# module_decoding_a.net
KiCad netlist of a schematic drawn in EAGLE
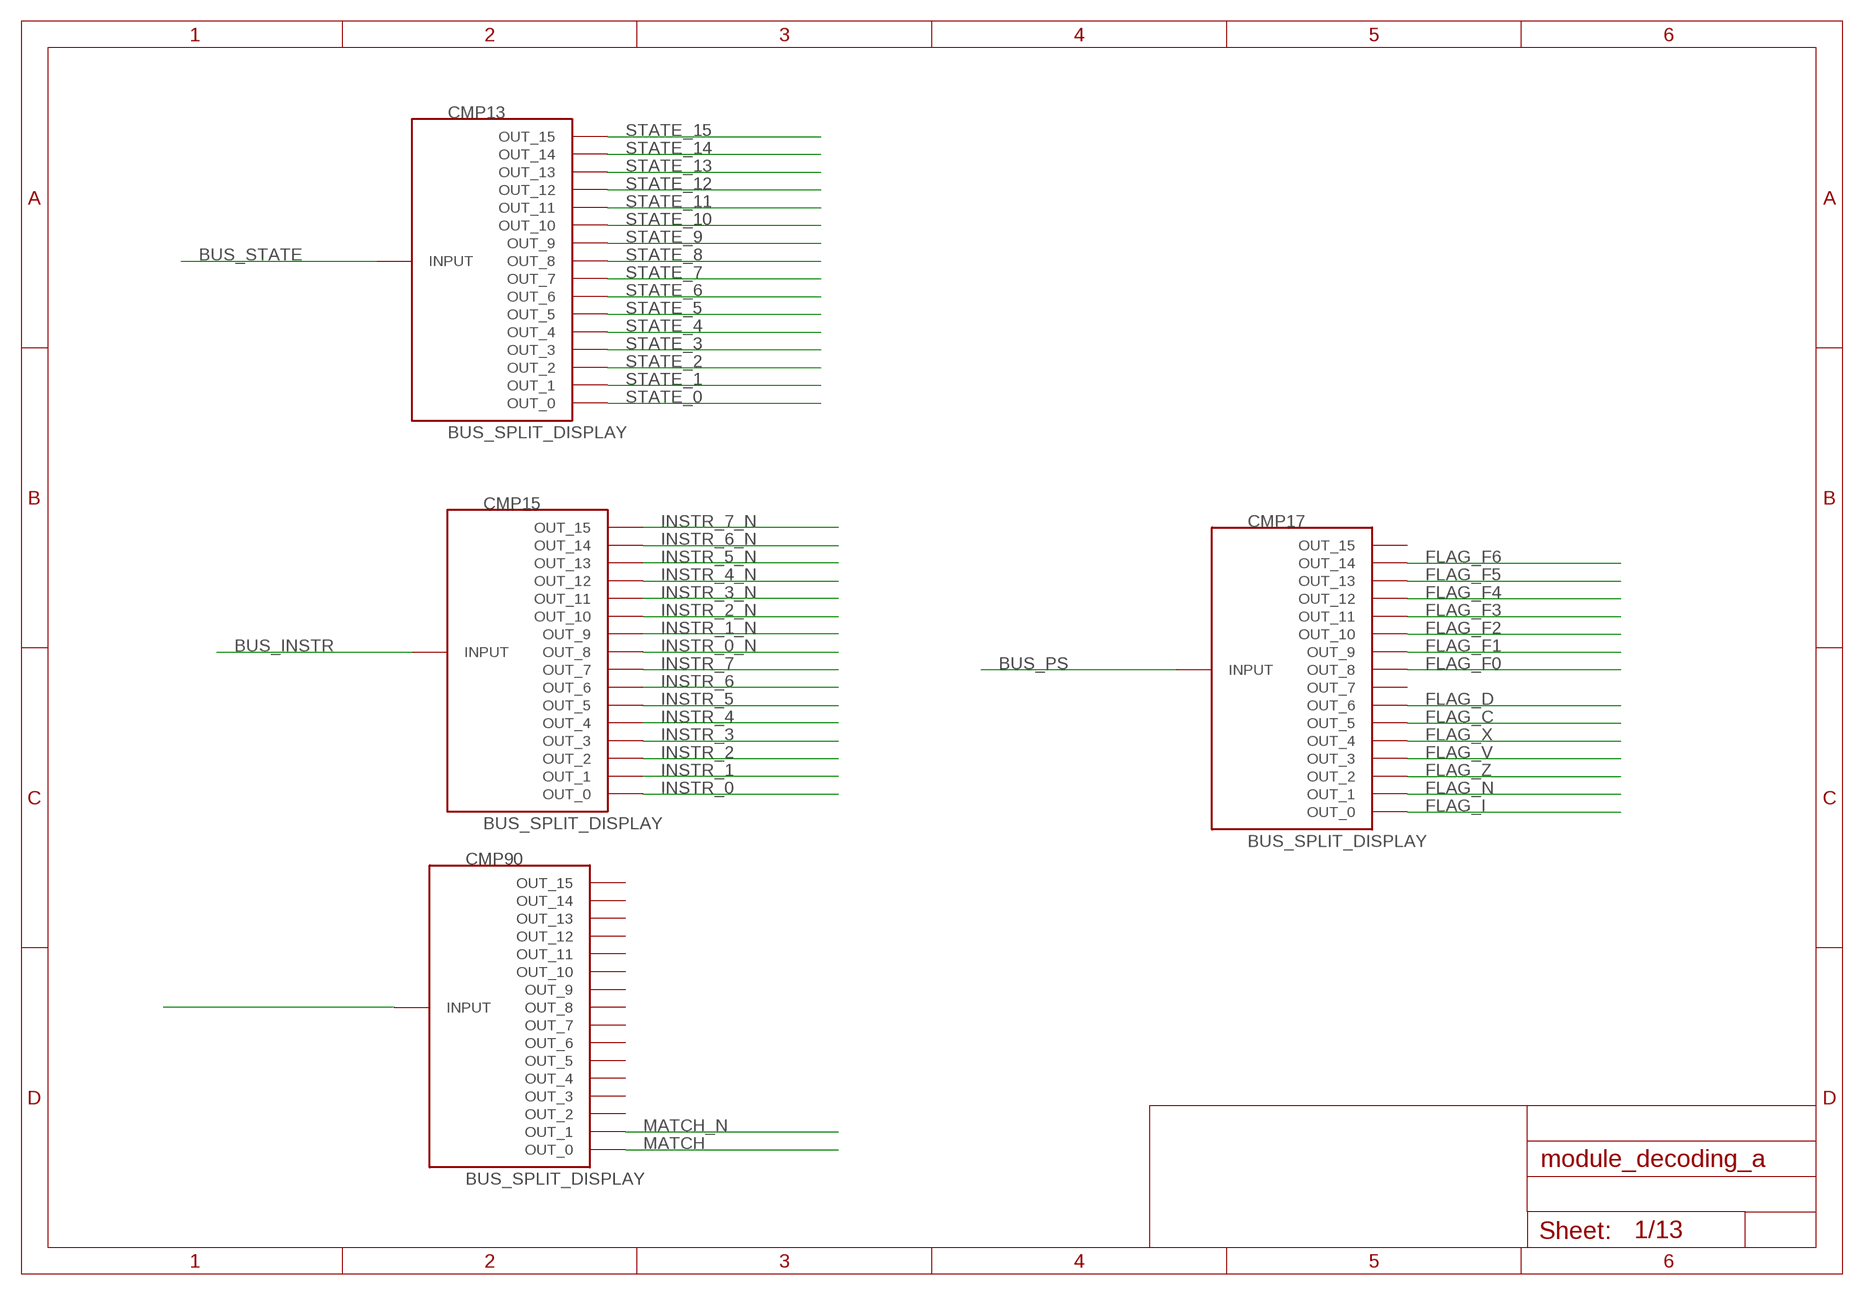
[diagram p0: schematic, sheet 1]
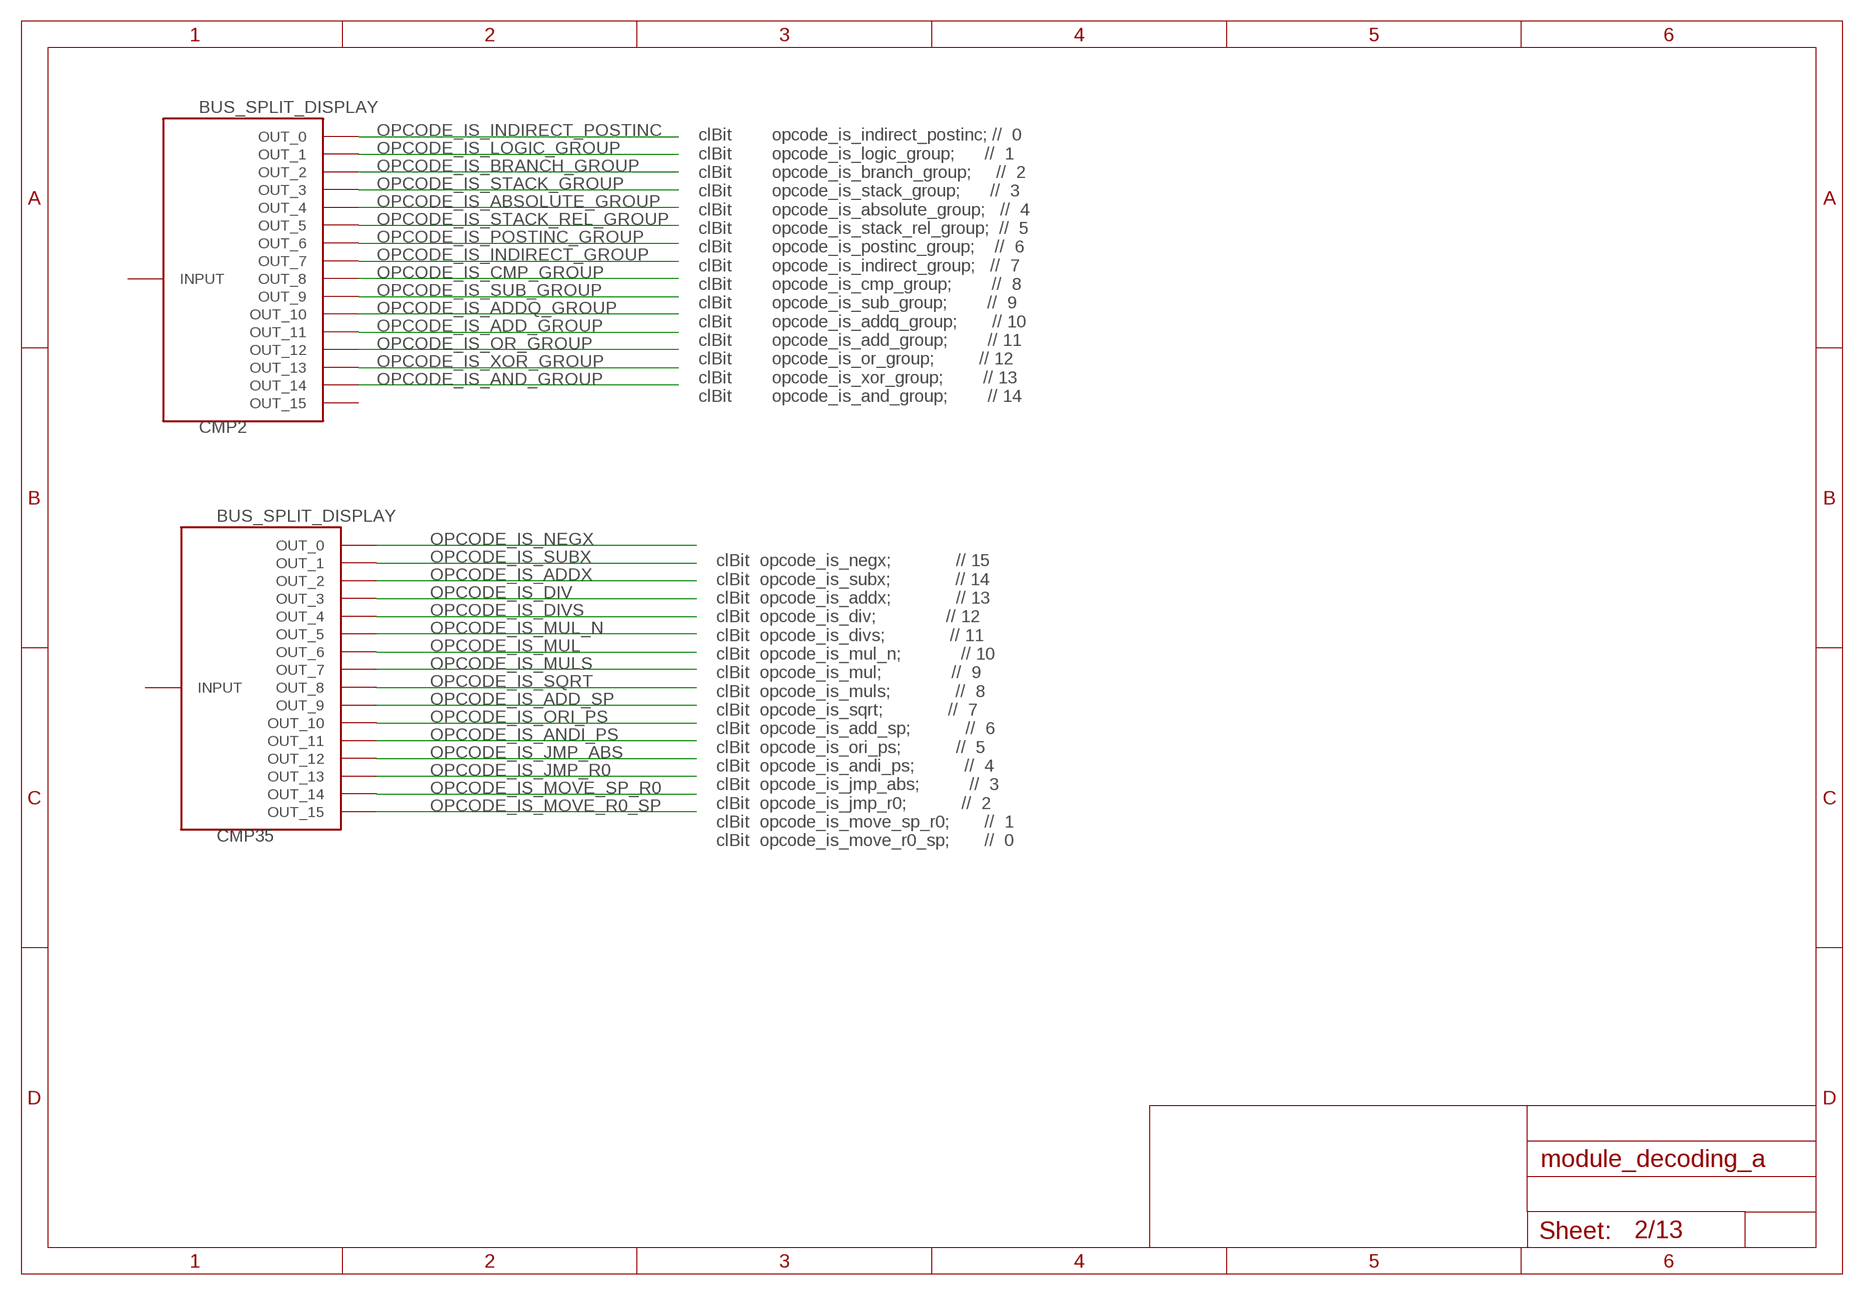
[diagram p1: schematic, sheet 2]
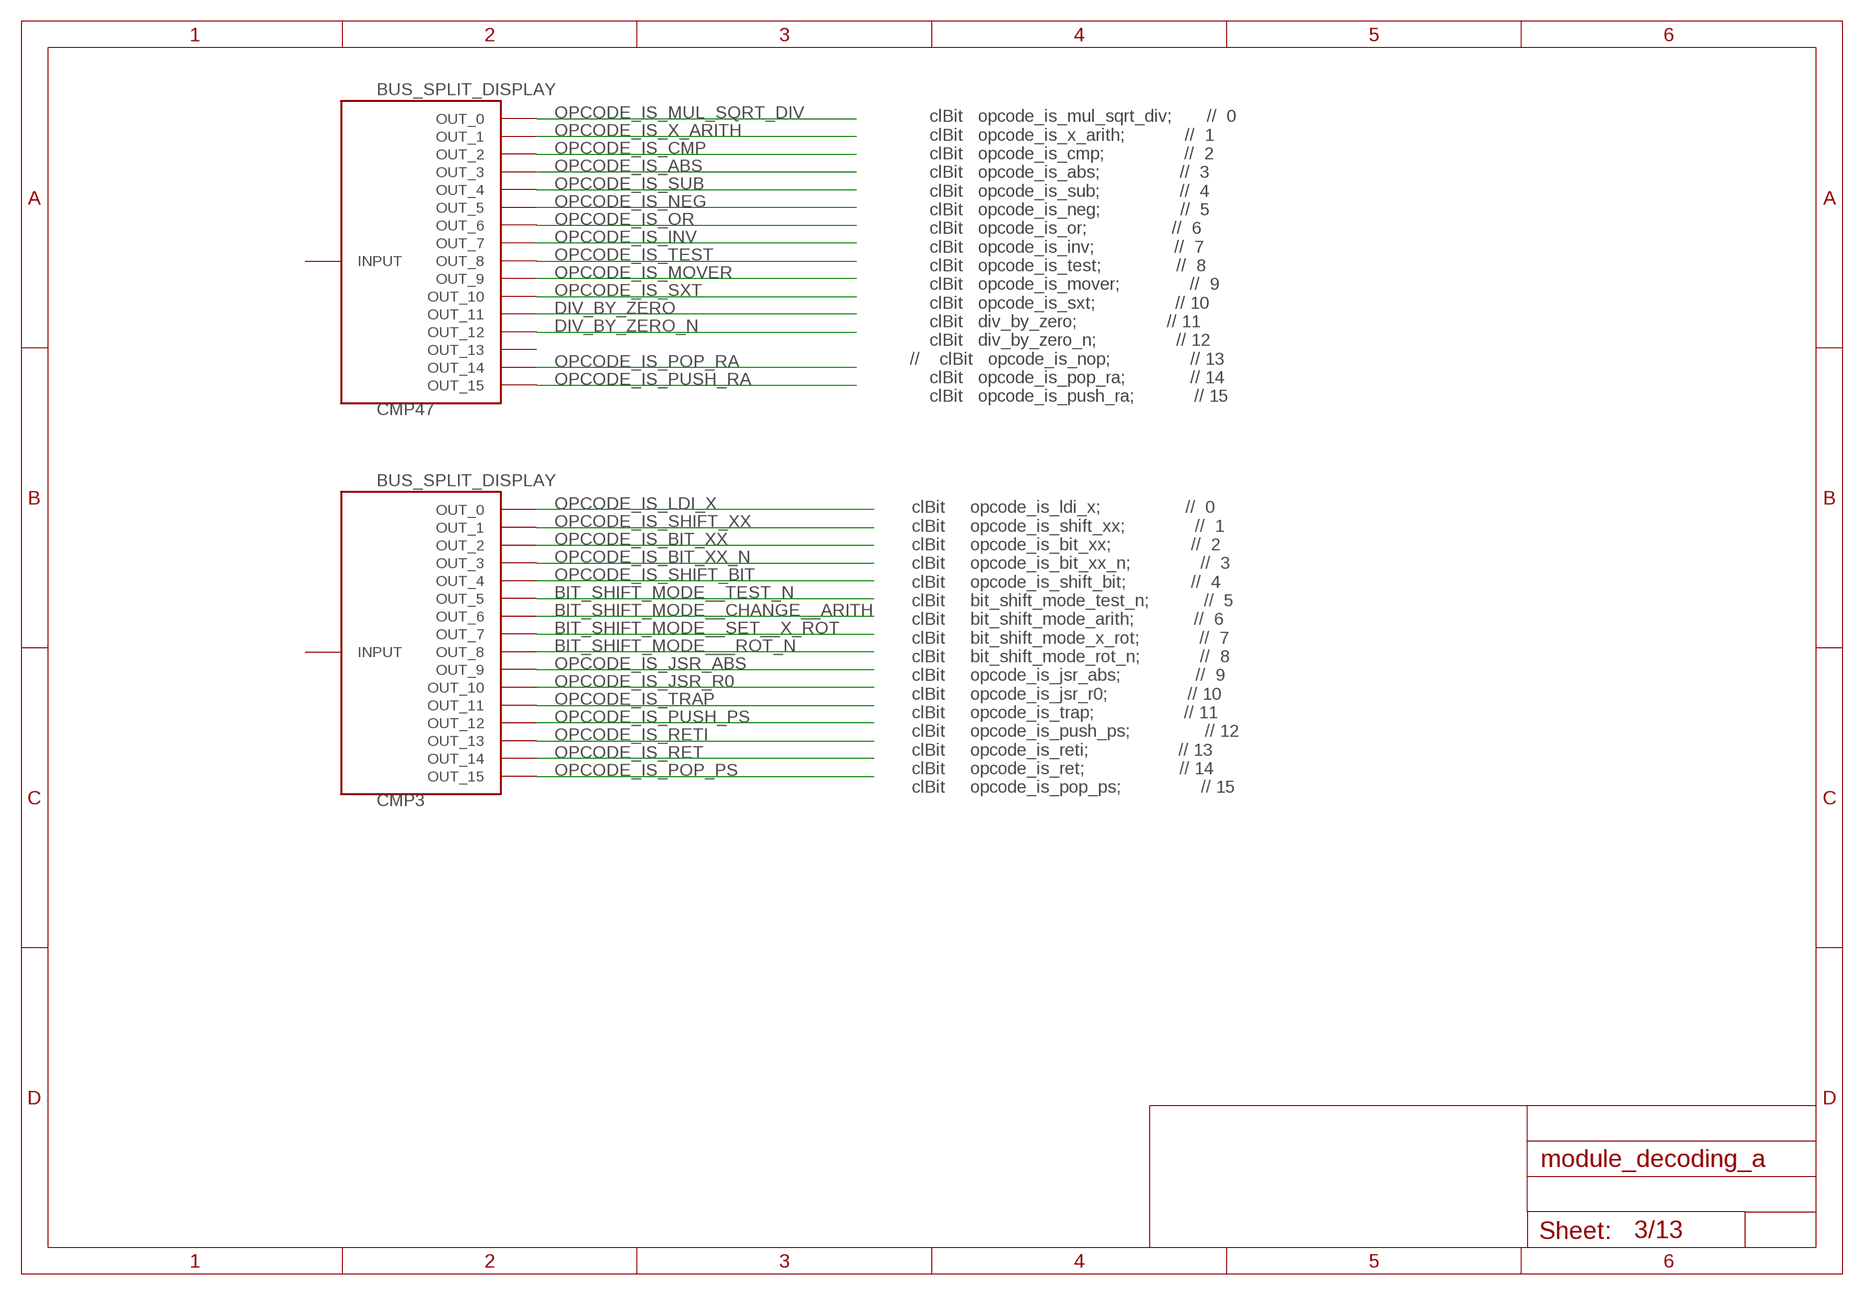
[diagram p2: schematic, sheet 3]
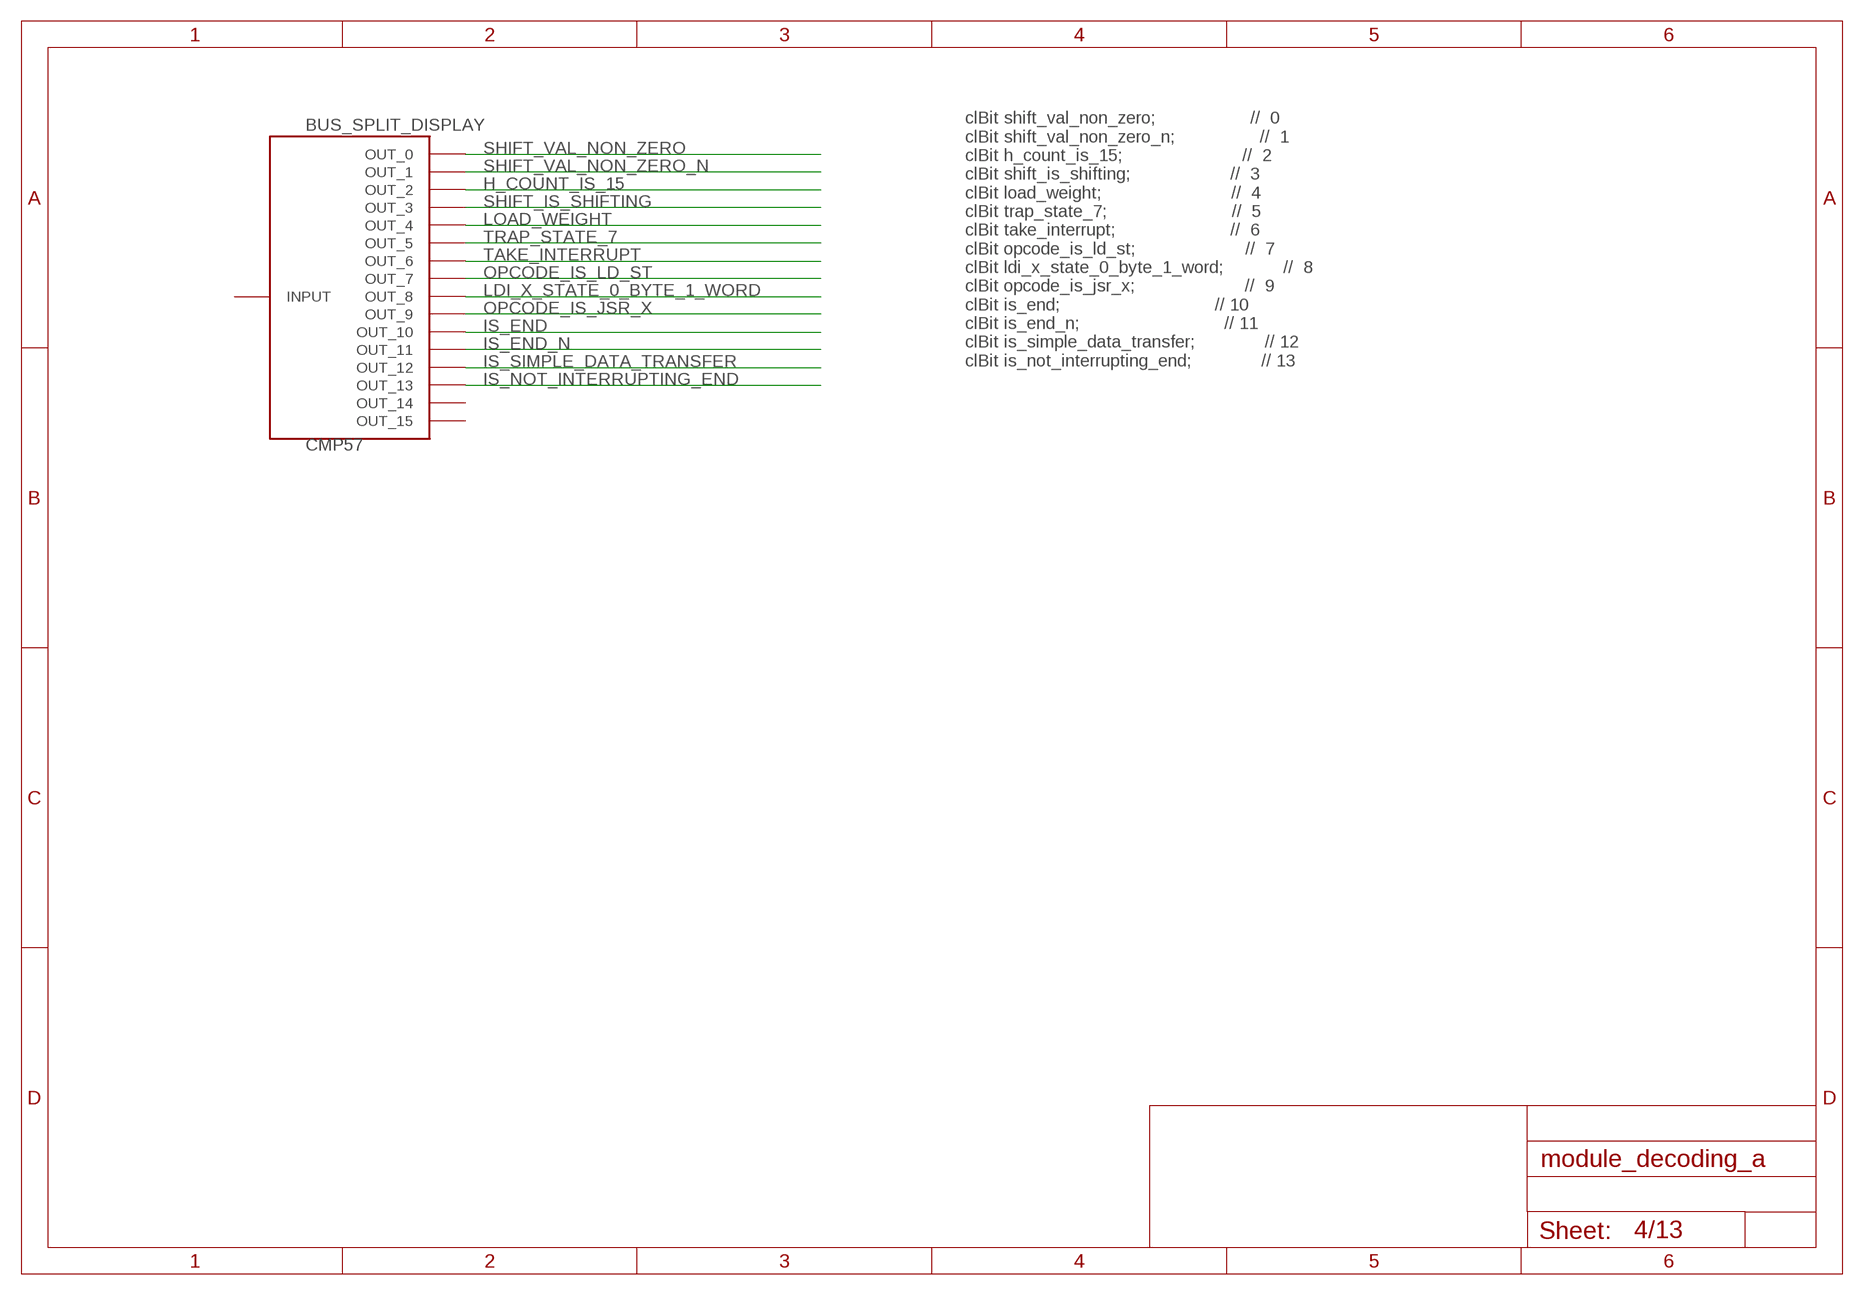
[diagram p3: schematic, sheet 4]
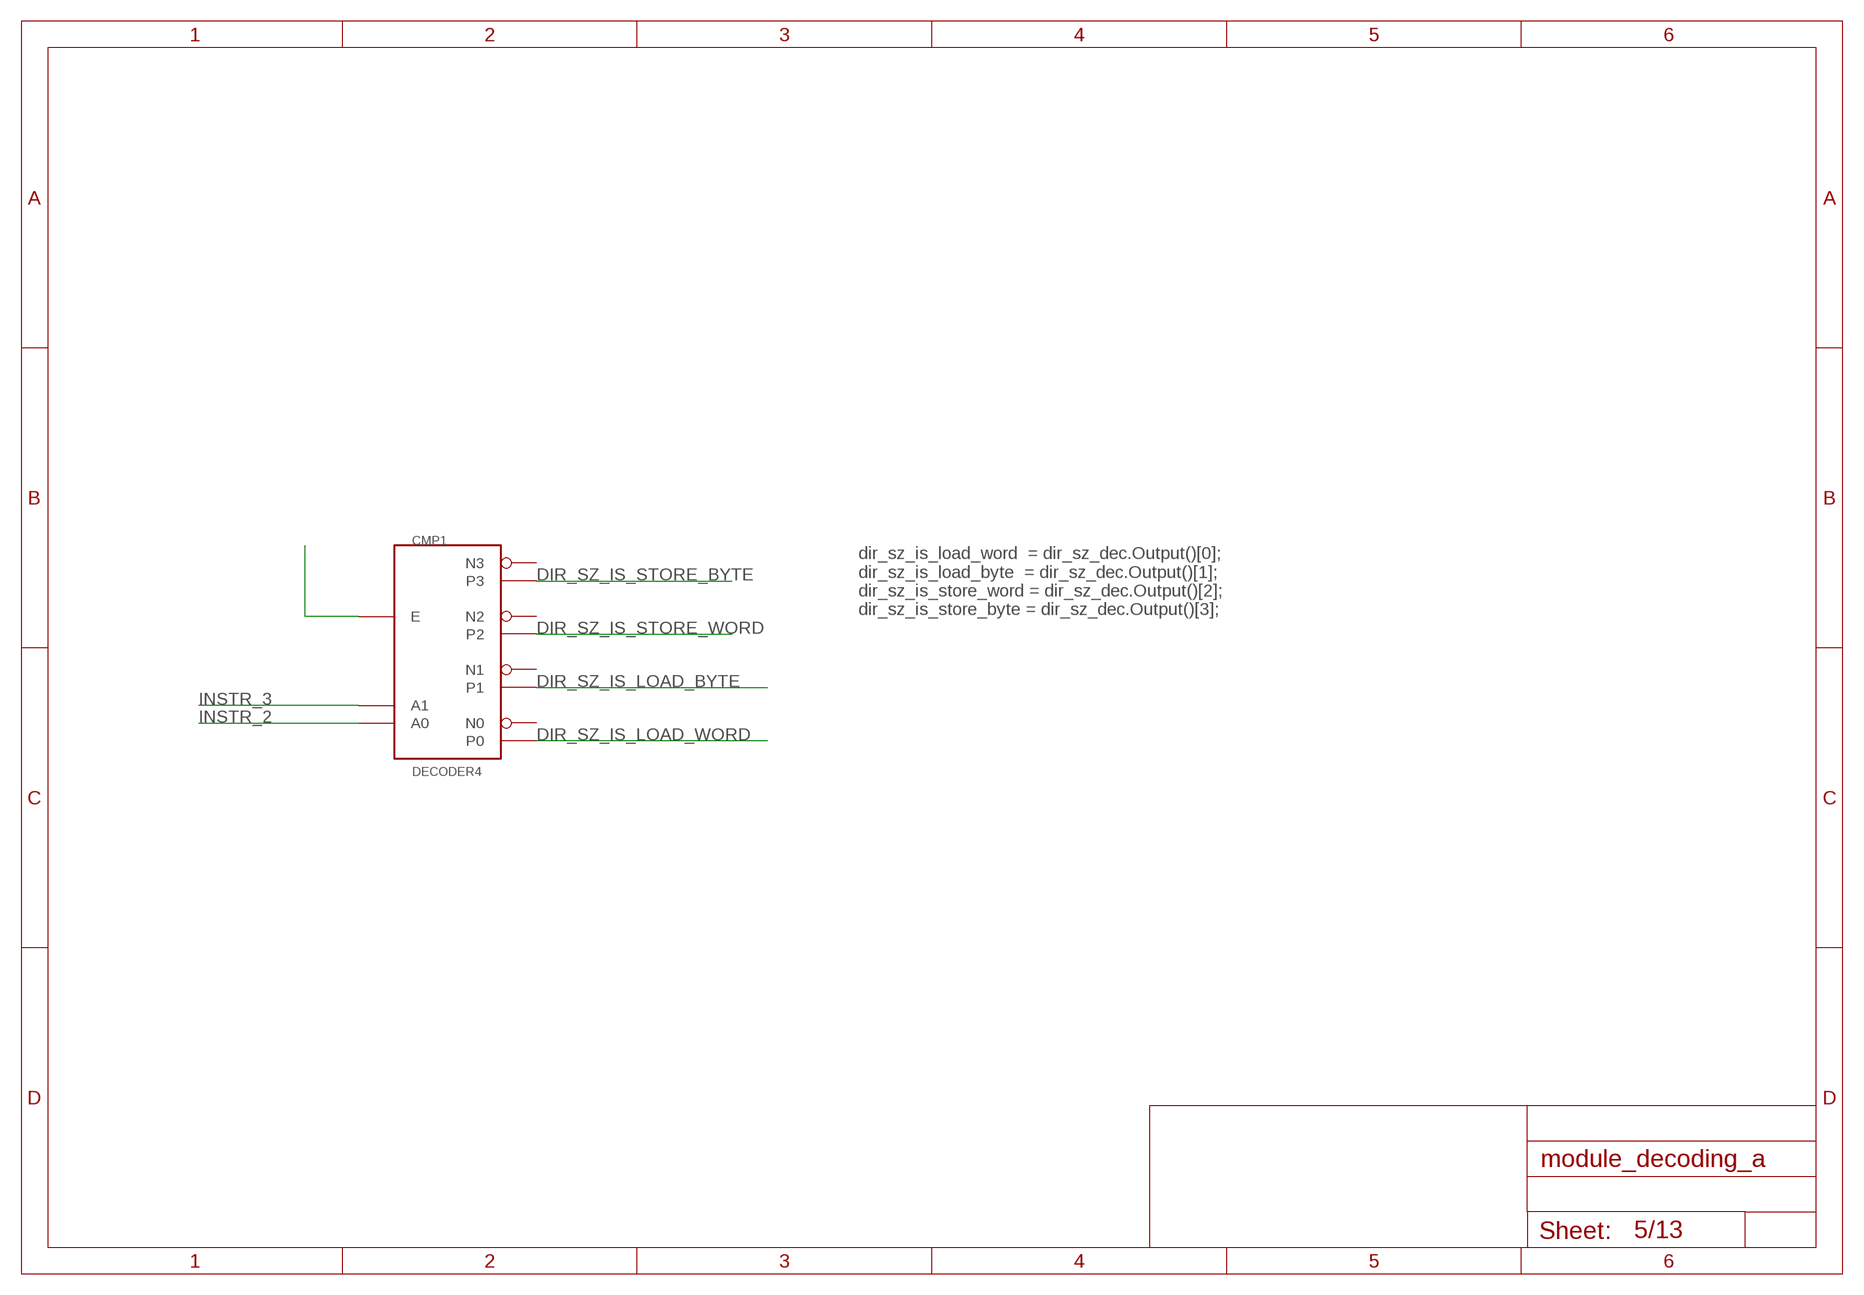
[diagram p4: schematic, sheet 5]
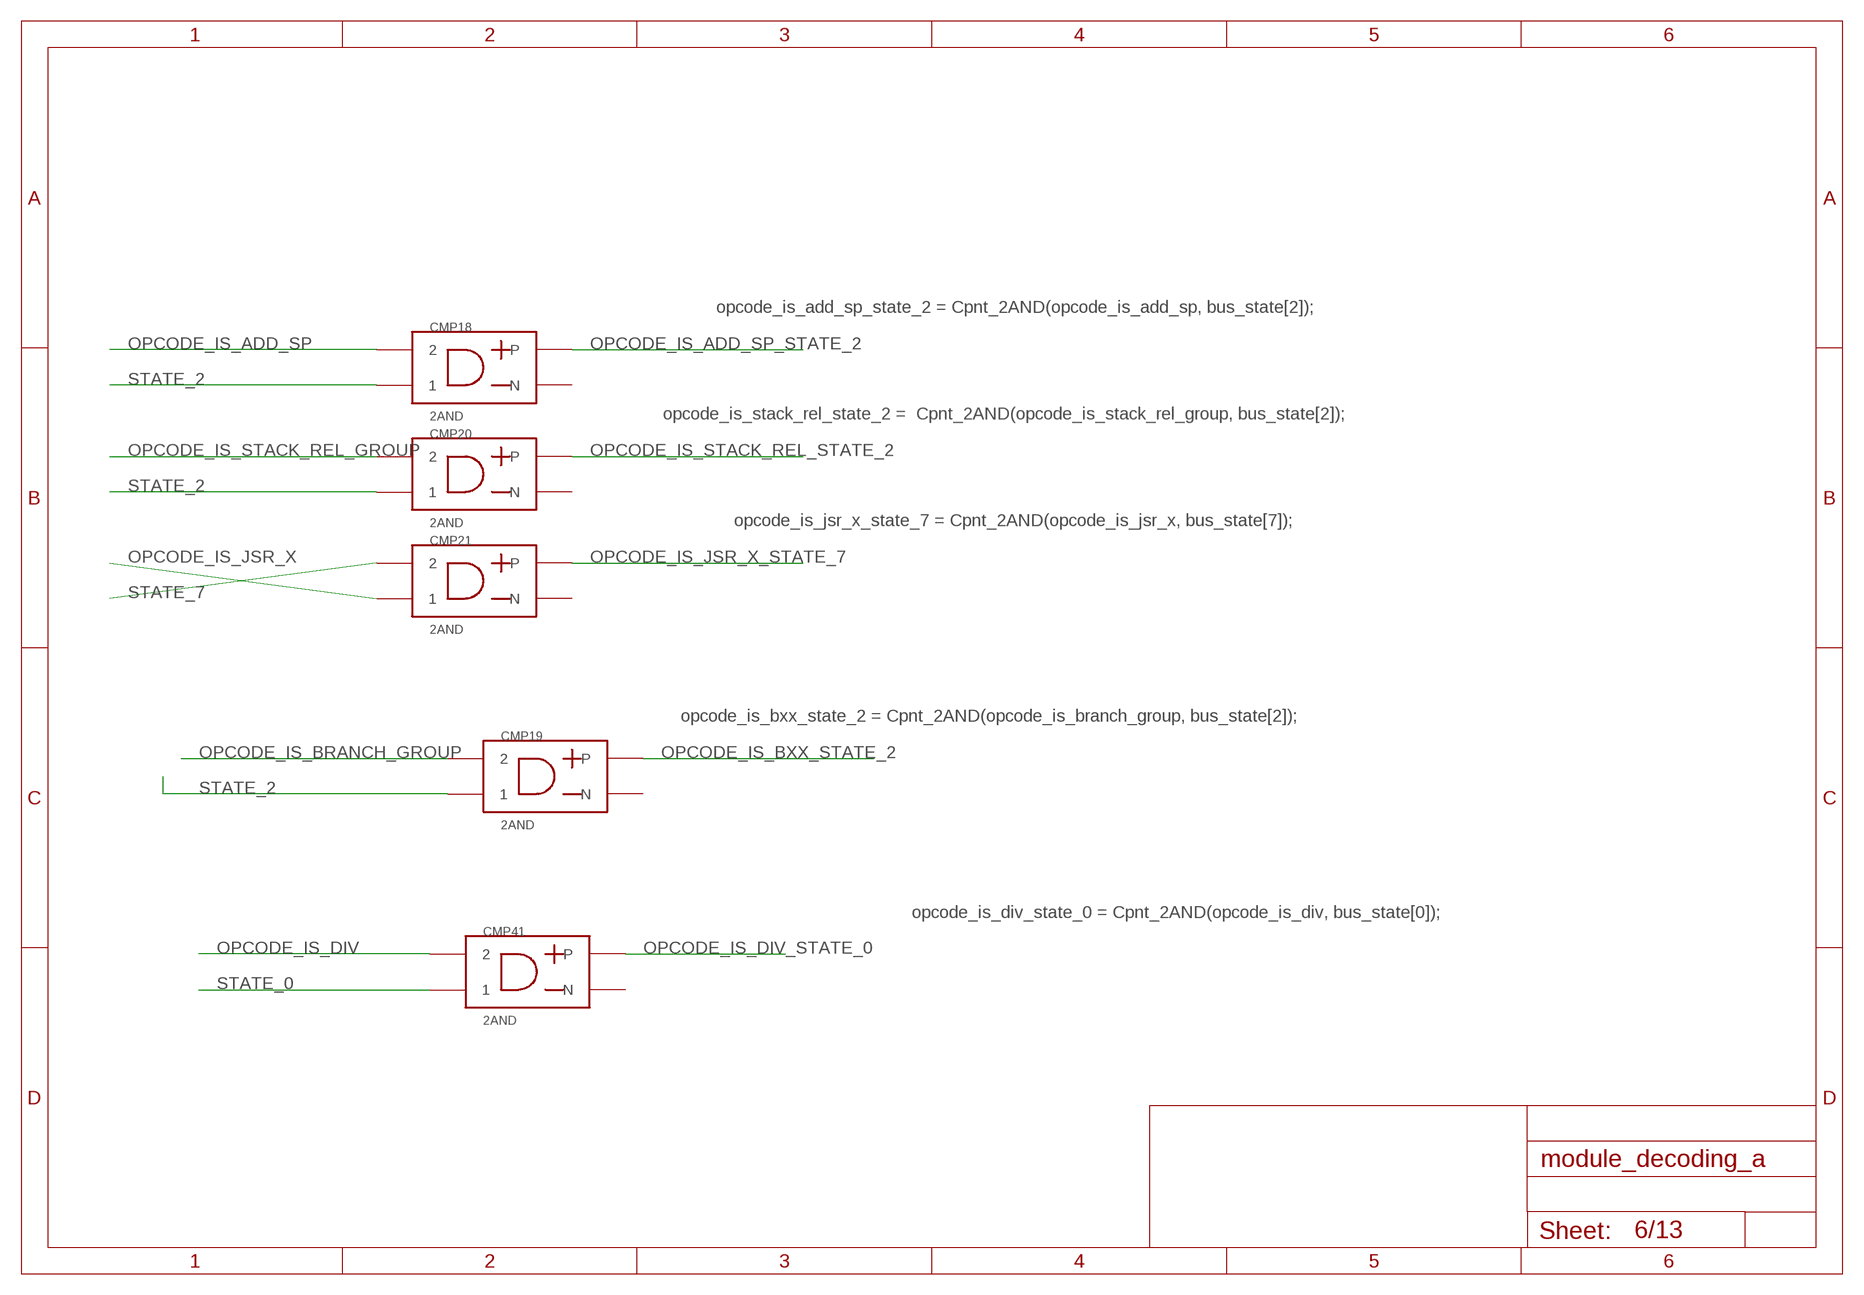
[diagram p5: schematic, sheet 6]
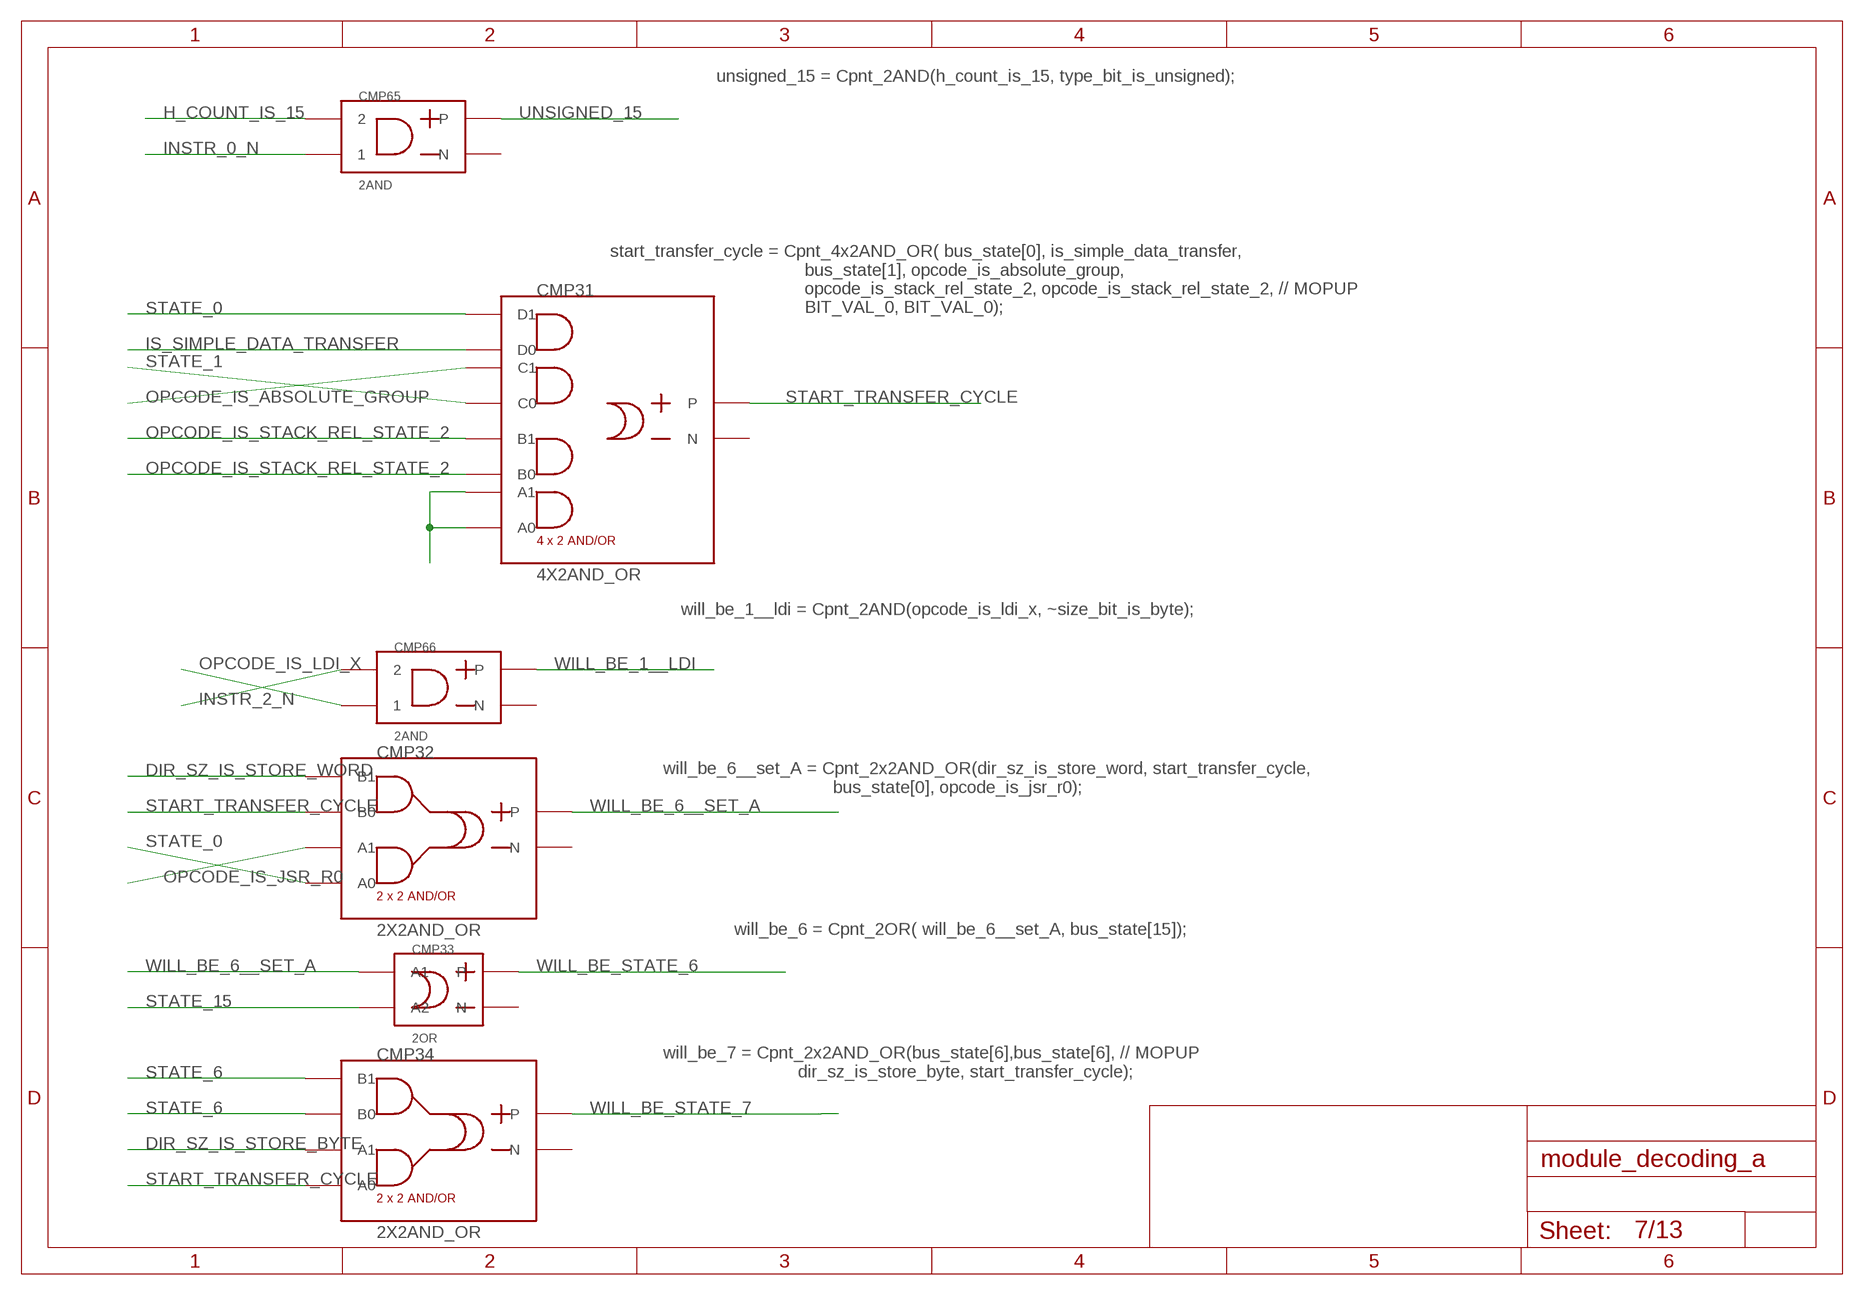
[diagram p6: schematic, sheet 7]
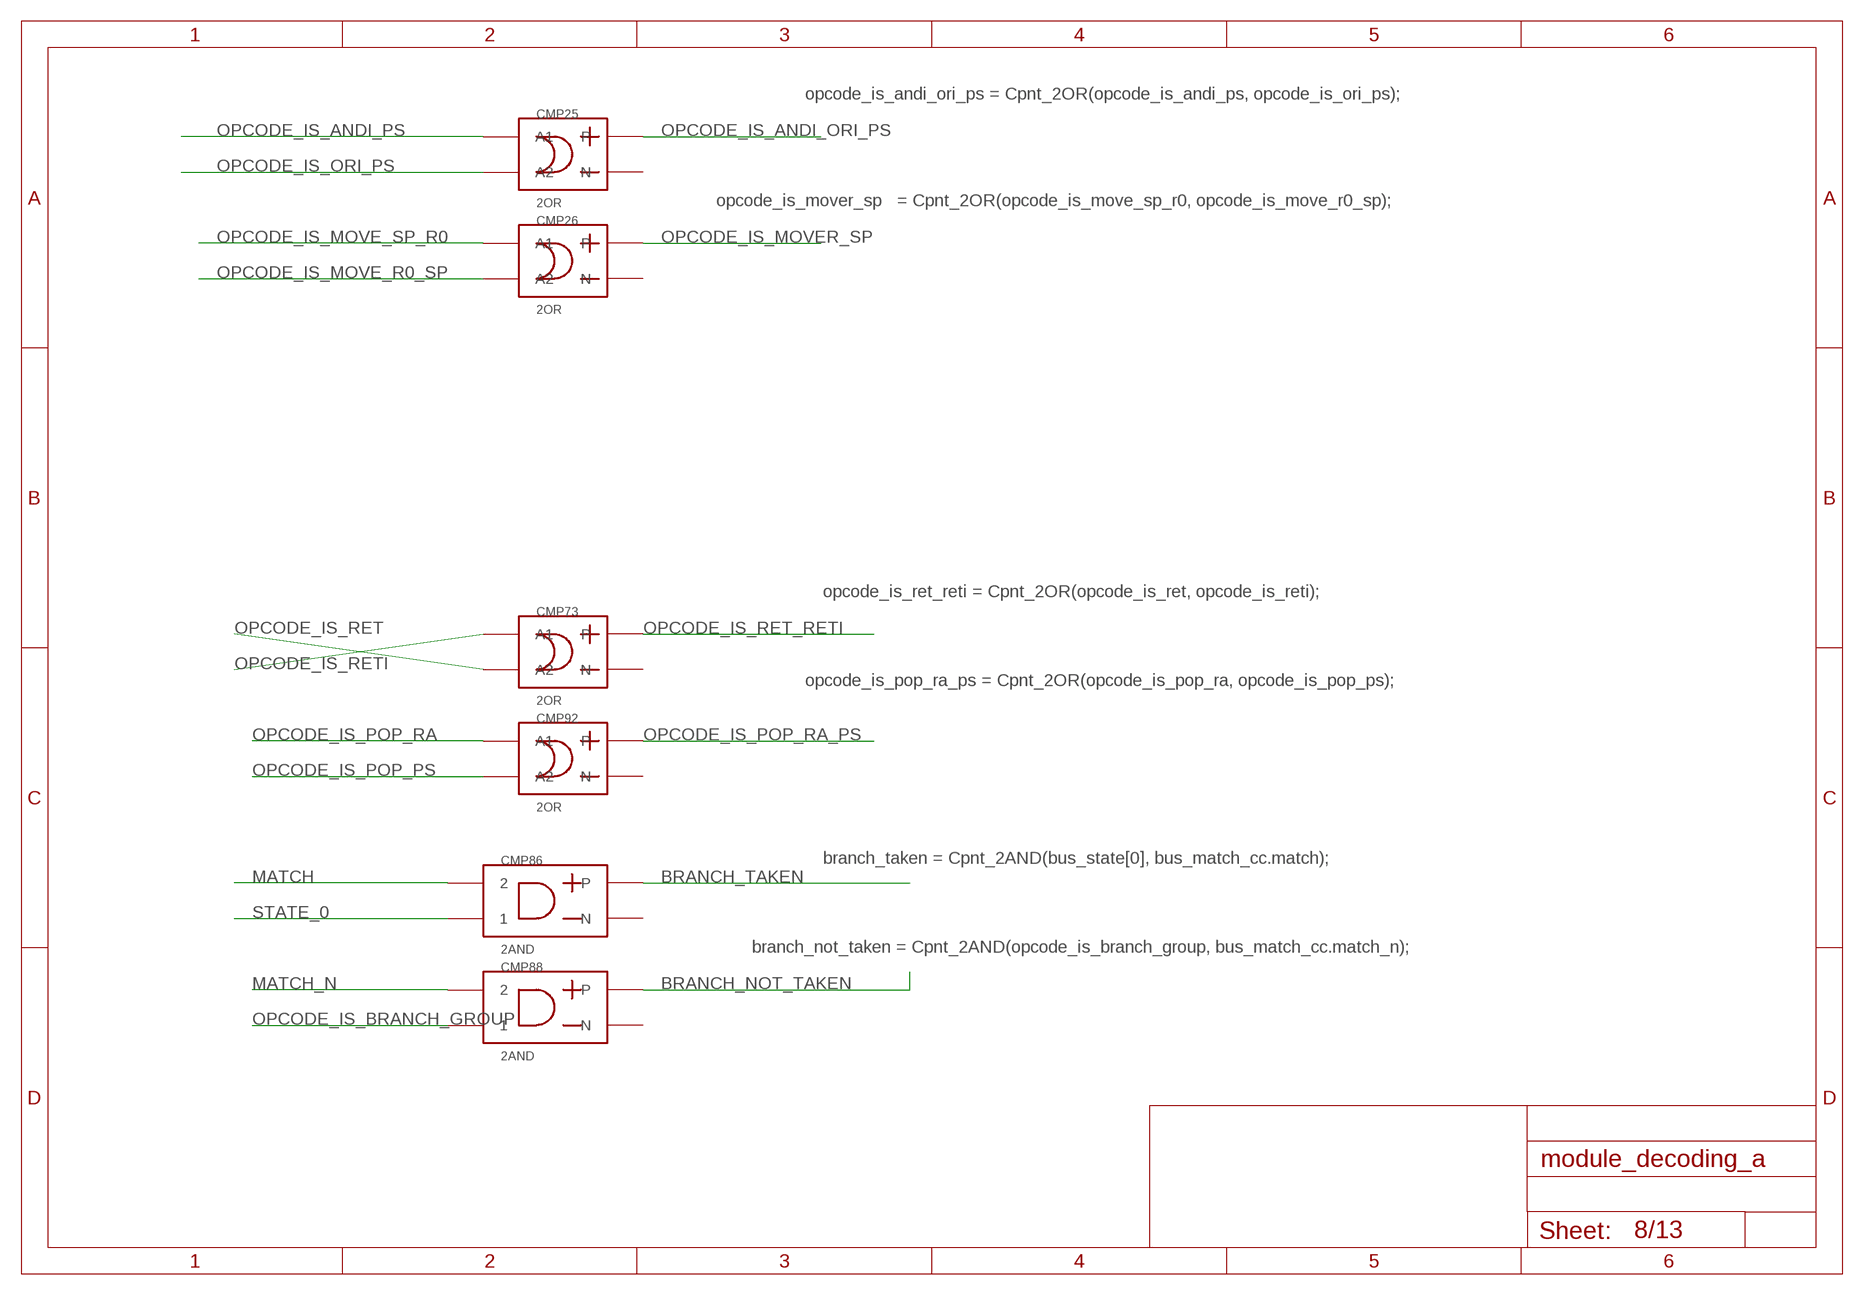
[diagram p7: schematic, sheet 8]
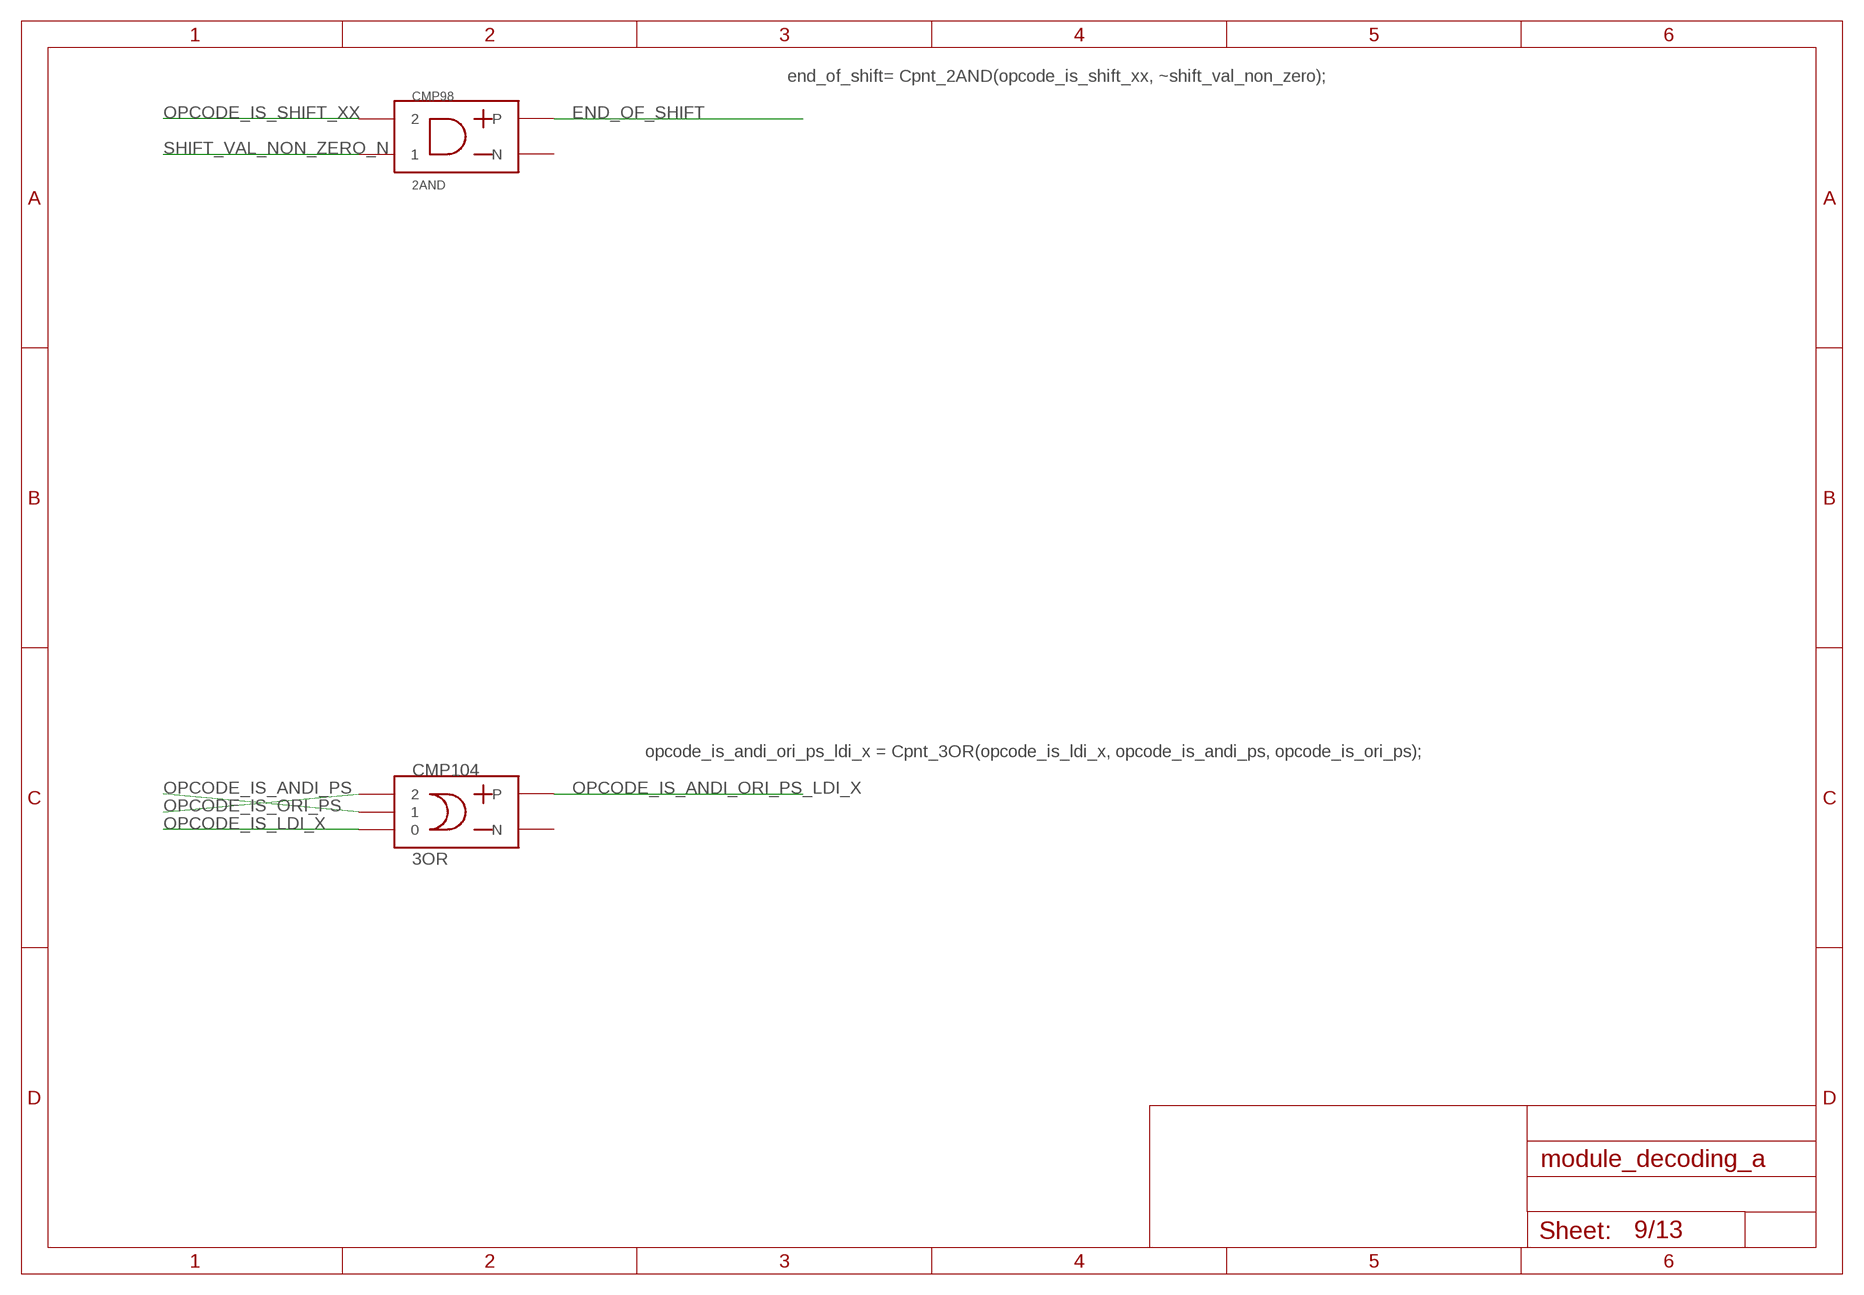
[diagram p8: schematic, sheet 9]
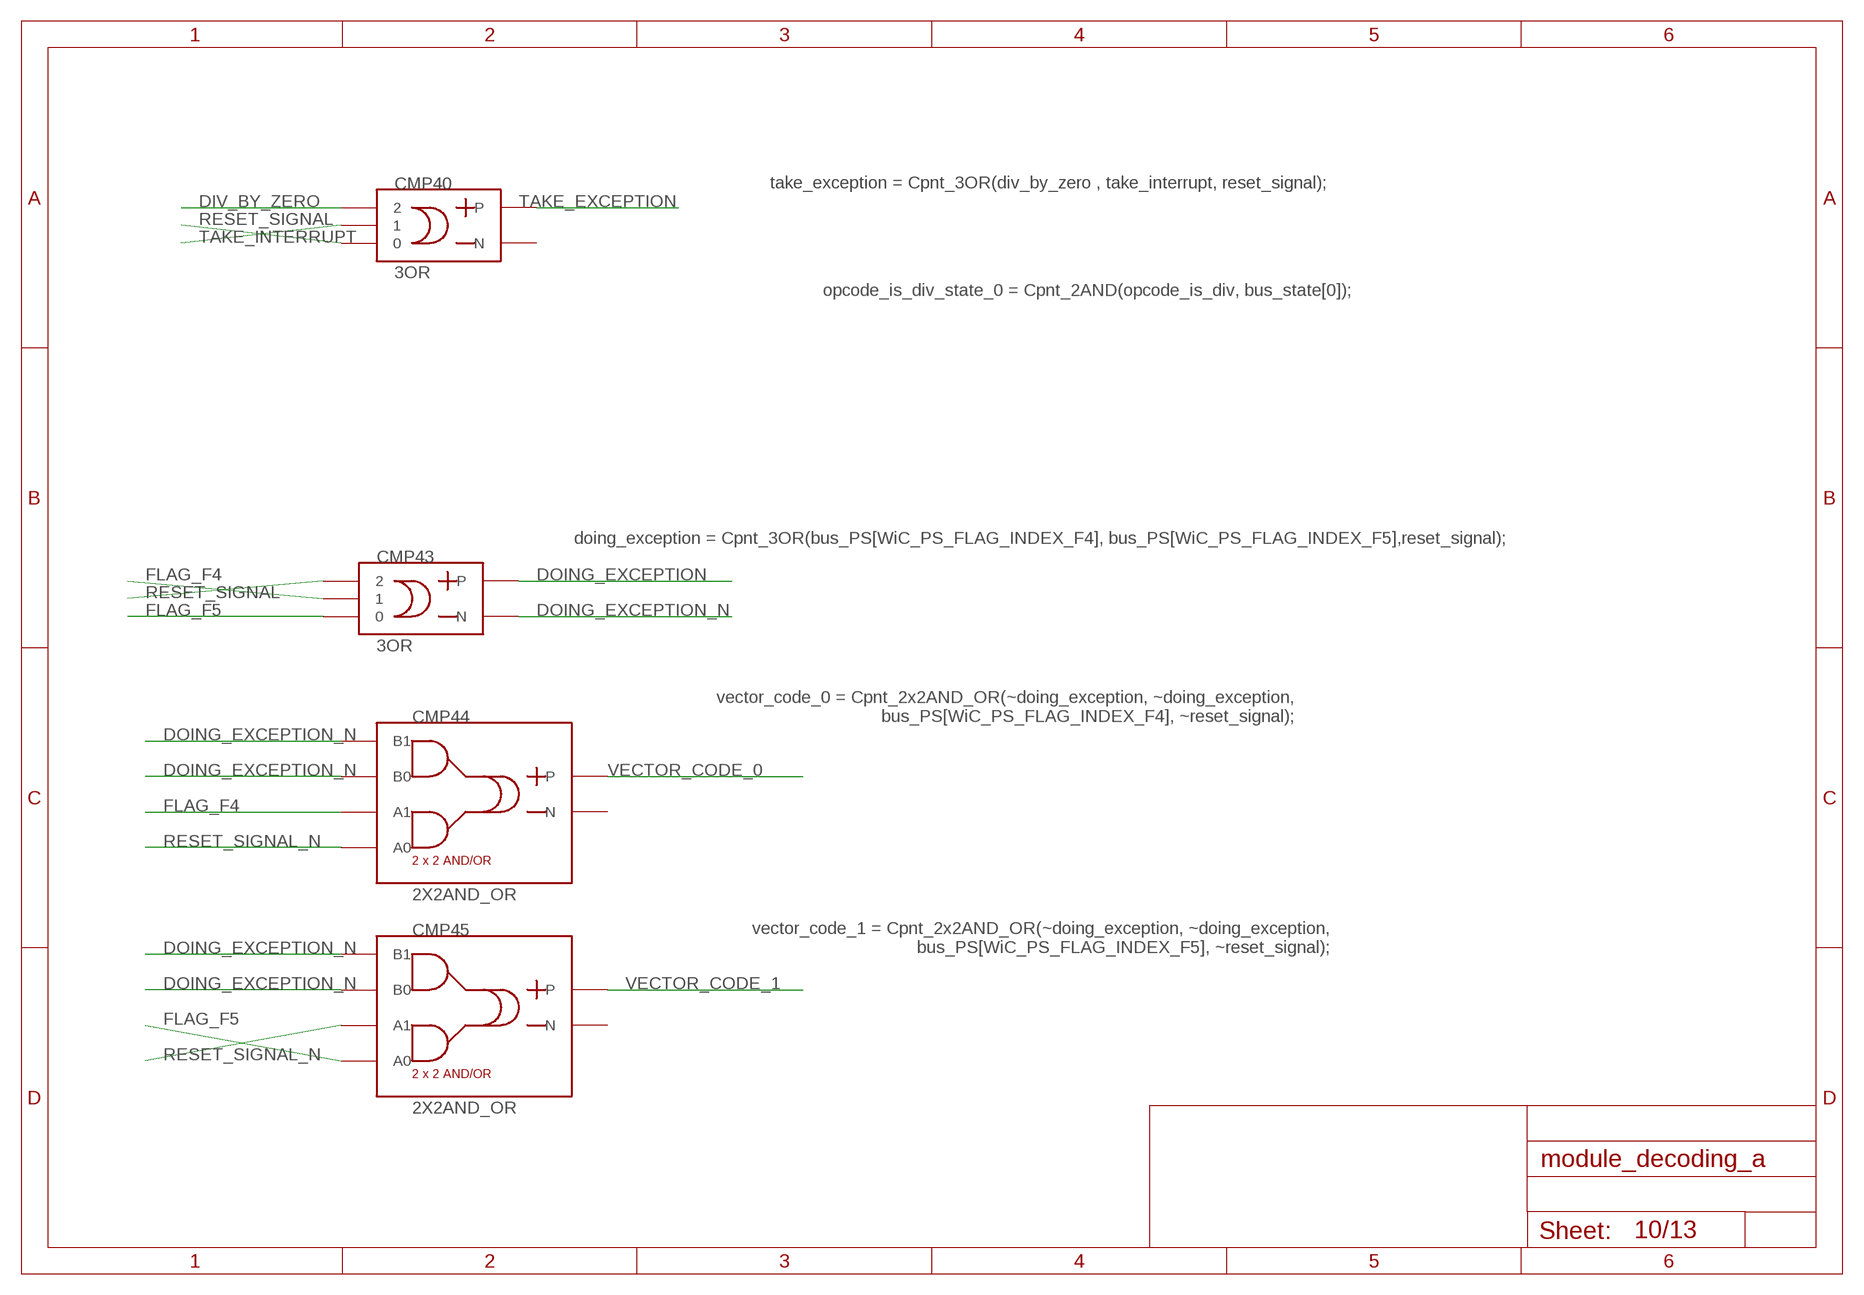
[diagram p9: schematic, sheet 10]
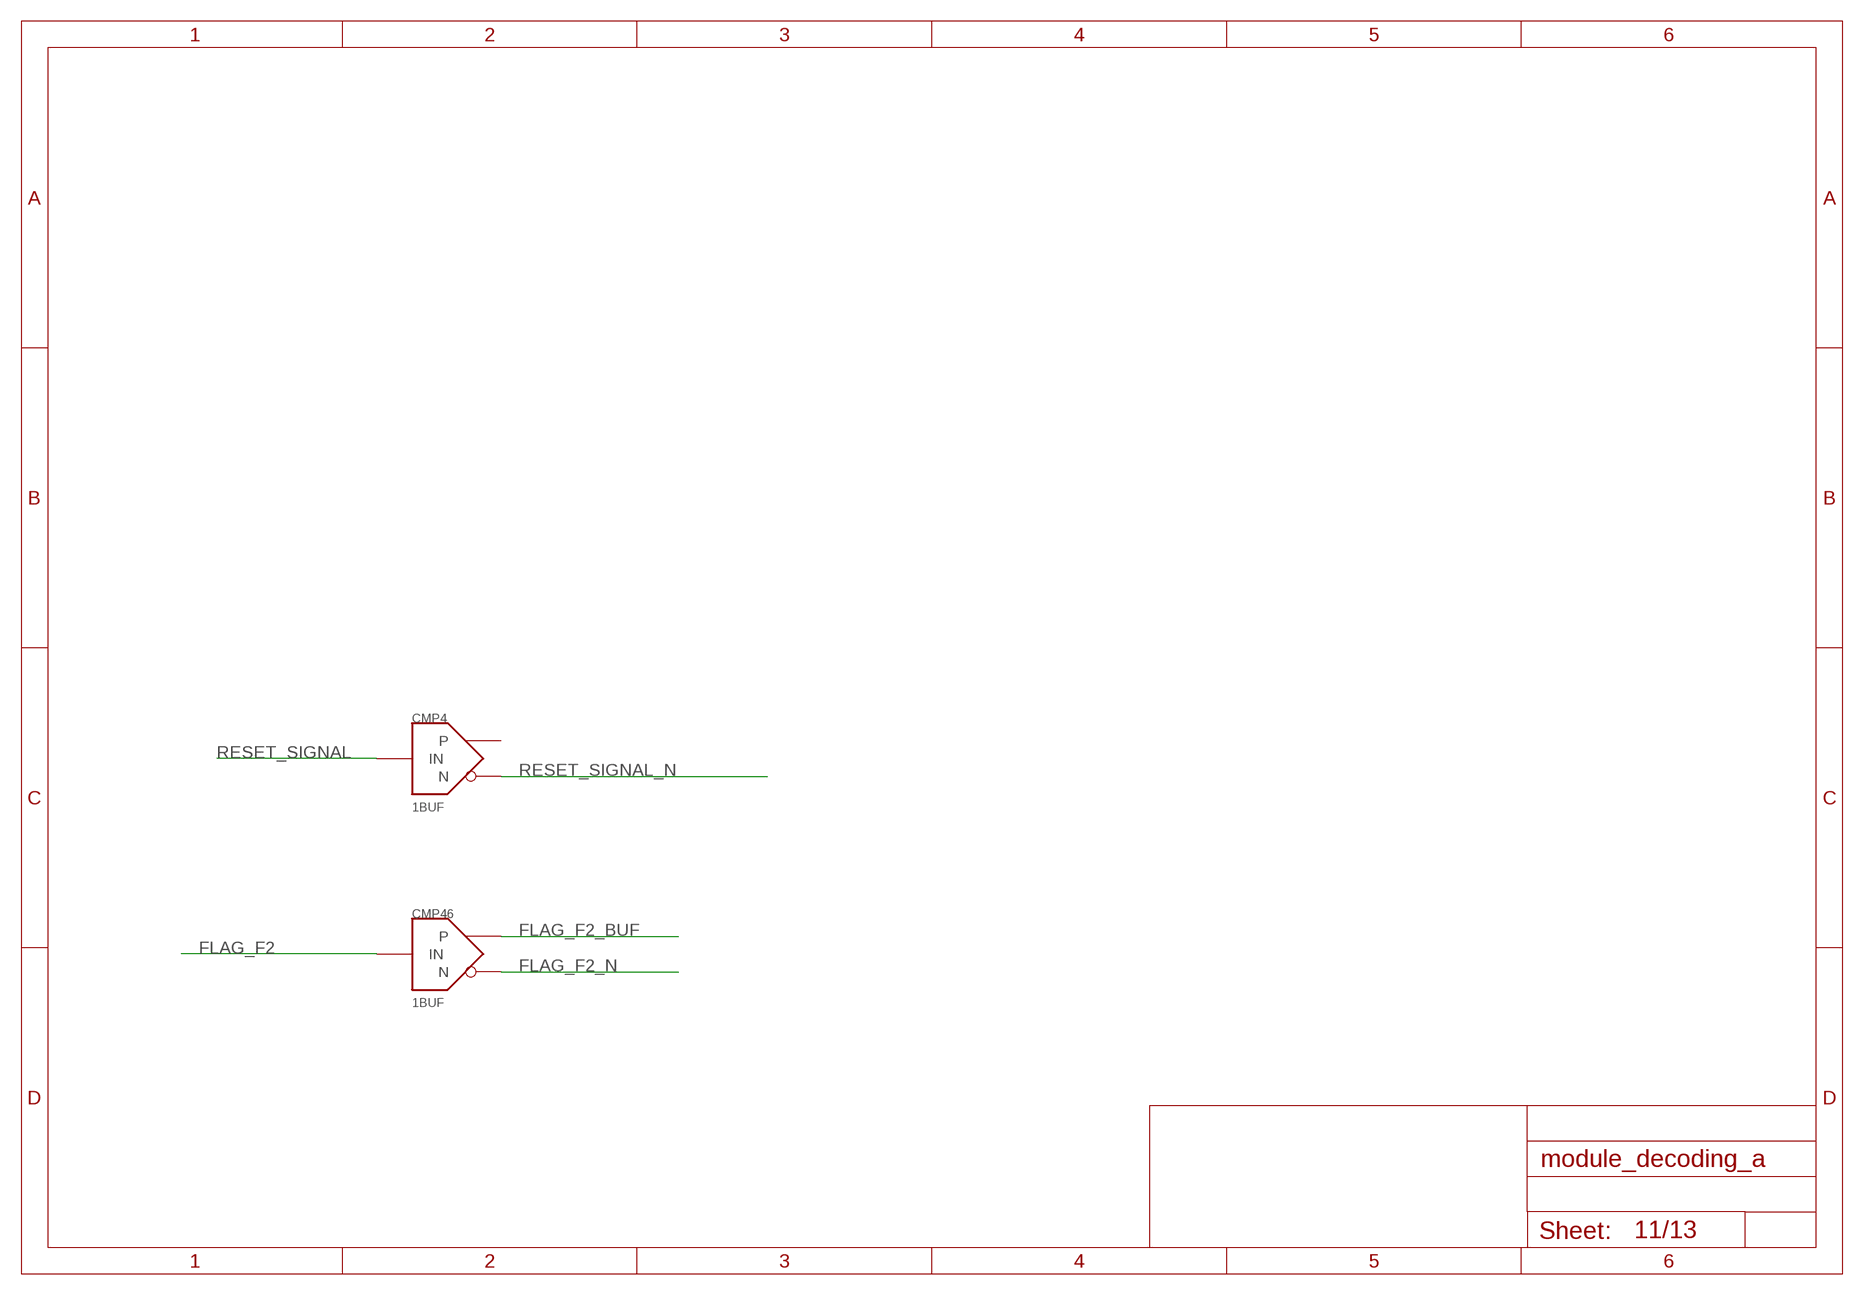
[diagram p10: schematic, sheet 11]
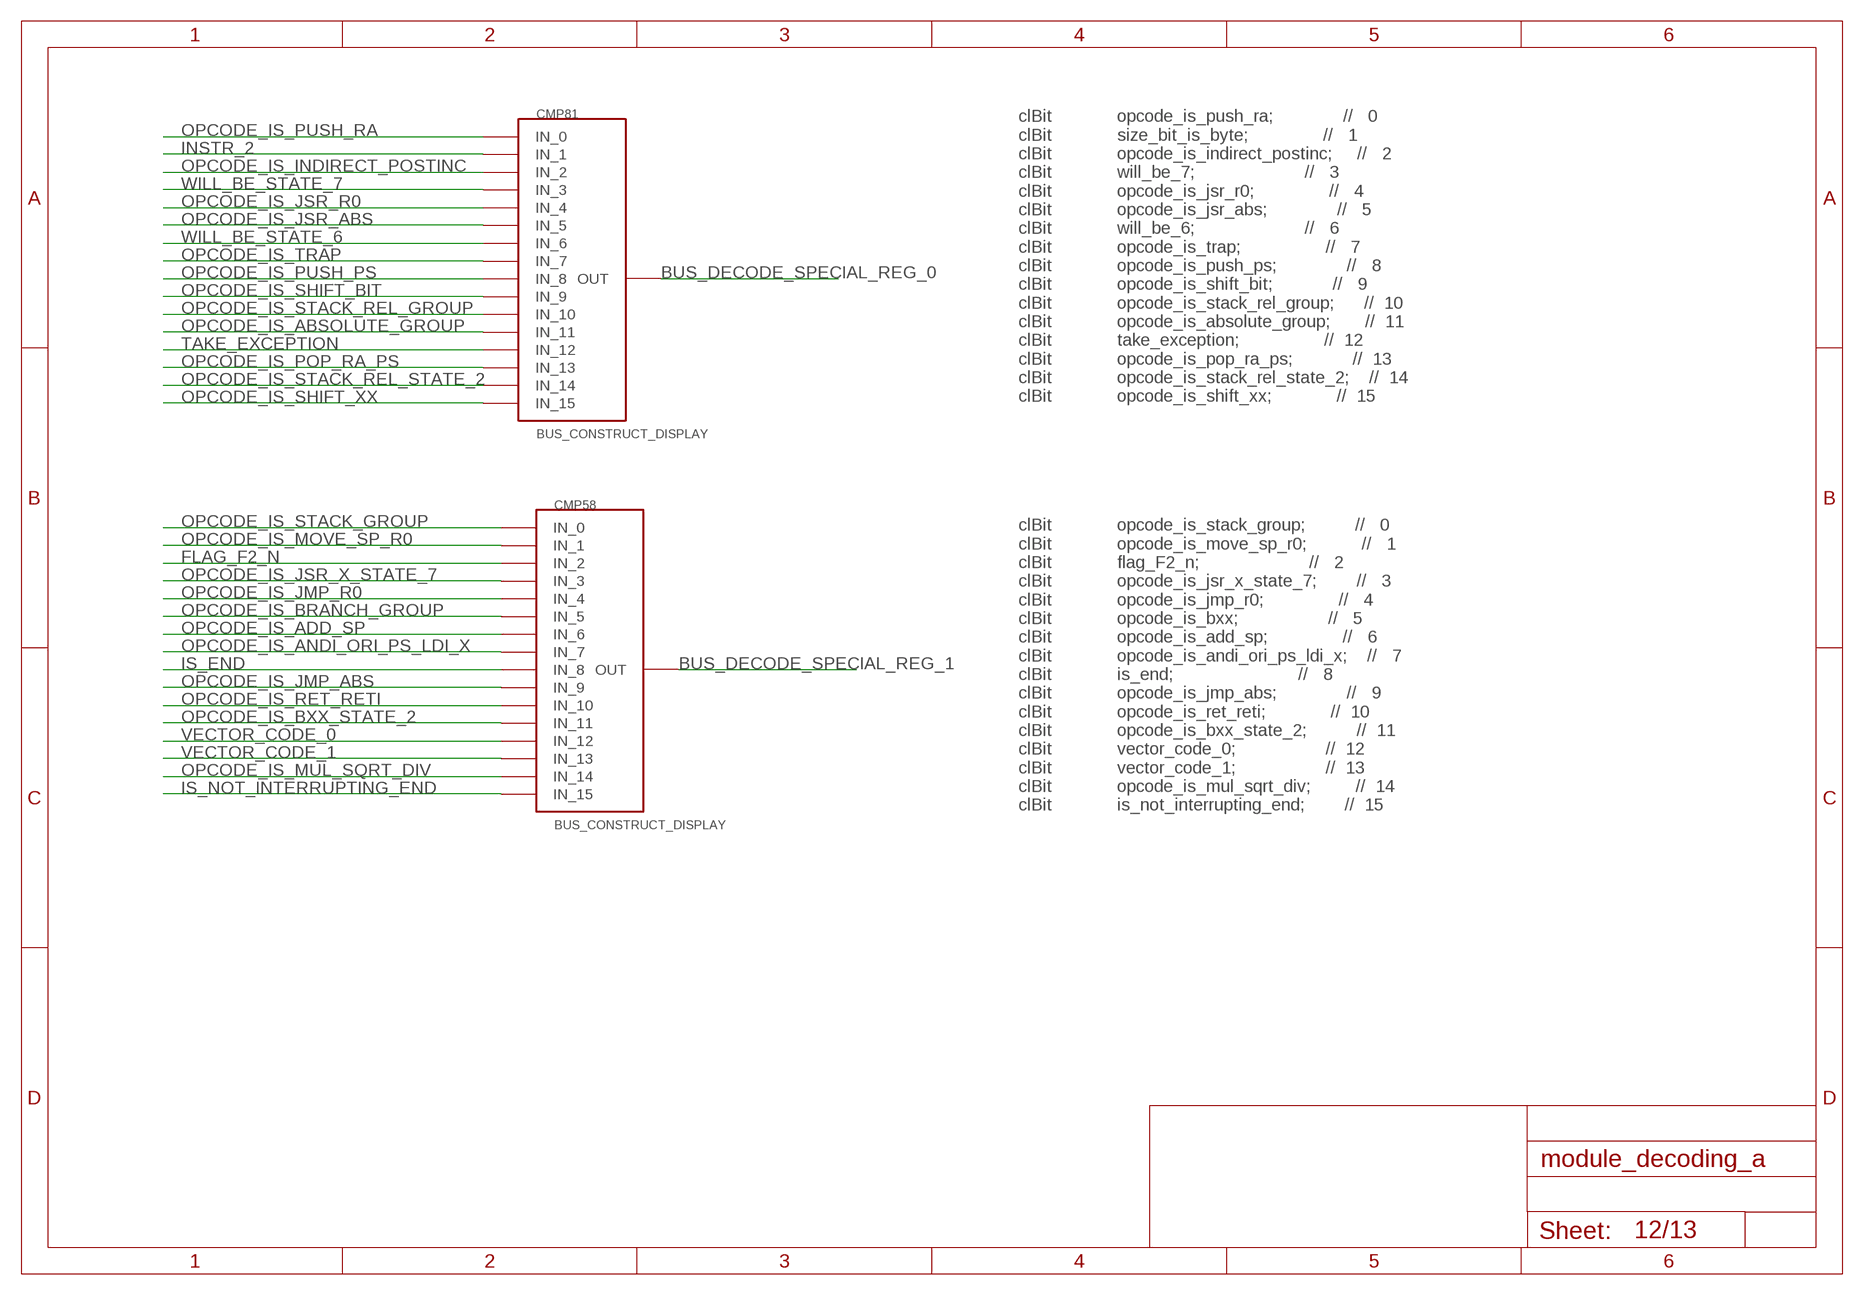
[diagram p11: schematic, sheet 12]
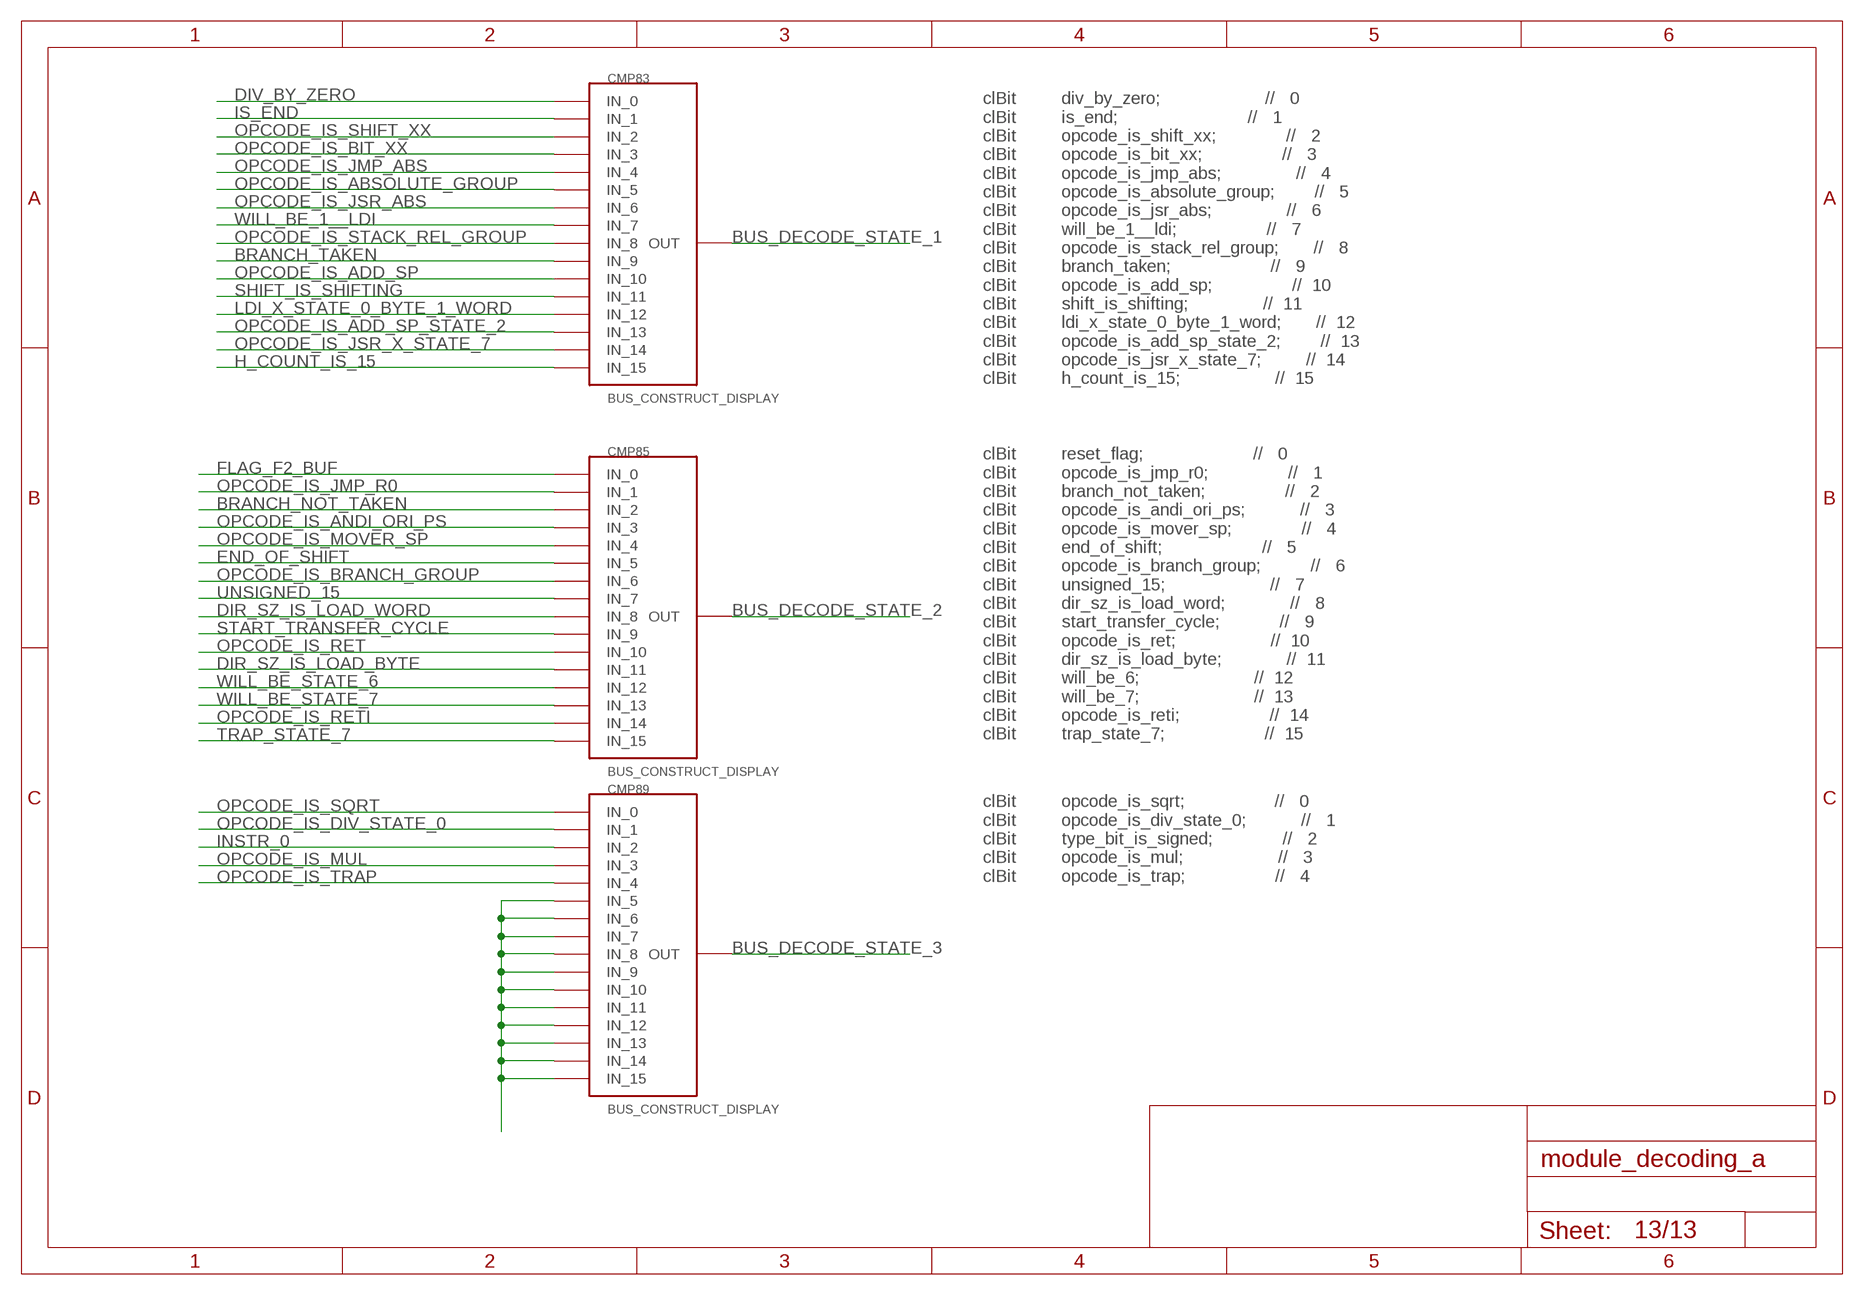
[diagram p12: schematic, sheet 13]

(export (version "E")
  (design (tool "Eeschema 10.0.6"))
  (components
    (comp (ref "CMP57")
      (value "BUS_SPLIT_DISPLAY")
      (footprint "eagle-import:BUS_SPLIT_DISPLAY")
      (libsource (lib "eagle-import") (part "BUS_SPLIT_DISPLAY"))
    )
    (comp (ref "CMP58")
      (value "BUS_CONSTRUCT_DISPLAY")
      (footprint "eagle-import:BUS_SPLIT_DISPLAY")
      (libsource (lib "eagle-import") (part "BUS_CONSTRUCT_DISPLAY"))
    )
    (comp (ref "CMP81")
      (value "BUS_CONSTRUCT_DISPLAY")
      (footprint "eagle-import:BUS_SPLIT_DISPLAY")
      (libsource (lib "eagle-import") (part "BUS_CONSTRUCT_DISPLAY"))
    )
    (comp (ref "CMP98")
      (value "2AND")
      (footprint "eagle-import:2AND")
      (libsource (lib "eagle-import") (part "2AND"))
    )
    (comp (ref "CMP104")
      (value "3OR")
      (footprint "eagle-import:3OR")
      (libsource (lib "eagle-import") (part "3OR"))
    )
    (comp (ref "CMP4")
      (value "1BUF")
      (footprint "eagle-import:1BUF")
      (libsource (lib "eagle-import") (part "1BUF"))
    )
    (comp (ref "CMP46")
      (value "1BUF")
      (footprint "eagle-import:1BUF")
      (libsource (lib "eagle-import") (part "1BUF"))
    )
    (comp (ref "CMP2")
      (value "BUS_SPLIT_DISPLAY")
      (footprint "eagle-import:BUS_SPLIT_DISPLAY")
      (libsource (lib "eagle-import") (part "BUS_SPLIT_DISPLAY"))
    )
    (comp (ref "CMP35")
      (value "BUS_SPLIT_DISPLAY")
      (footprint "eagle-import:BUS_SPLIT_DISPLAY")
      (libsource (lib "eagle-import") (part "BUS_SPLIT_DISPLAY"))
    )
    (comp (ref "CMP25")
      (value "2OR")
      (footprint "eagle-import:2OR")
      (libsource (lib "eagle-import") (part "2OR"))
    )
    (comp (ref "CMP26")
      (value "2OR")
      (footprint "eagle-import:2OR")
      (libsource (lib "eagle-import") (part "2OR"))
    )
    (comp (ref "CMP73")
      (value "2OR")
      (footprint "eagle-import:2OR")
      (libsource (lib "eagle-import") (part "2OR"))
    )
    (comp (ref "CMP86")
      (value "2AND")
      (footprint "eagle-import:2AND")
      (libsource (lib "eagle-import") (part "2AND"))
    )
    (comp (ref "CMP88")
      (value "2AND")
      (footprint "eagle-import:2AND")
      (libsource (lib "eagle-import") (part "2AND"))
    )
    (comp (ref "CMP92")
      (value "2OR")
      (footprint "eagle-import:2OR")
      (libsource (lib "eagle-import") (part "2OR"))
    )
    (comp (ref "CMP13")
      (value "BUS_SPLIT_DISPLAY")
      (footprint "eagle-import:BUS_SPLIT_DISPLAY")
      (libsource (lib "eagle-import") (part "BUS_SPLIT_DISPLAY"))
    )
    (comp (ref "CMP15")
      (value "BUS_SPLIT_DISPLAY")
      (footprint "eagle-import:BUS_SPLIT_DISPLAY")
      (libsource (lib "eagle-import") (part "BUS_SPLIT_DISPLAY"))
    )
    (comp (ref "CMP17")
      (value "BUS_SPLIT_DISPLAY")
      (footprint "eagle-import:BUS_SPLIT_DISPLAY")
      (libsource (lib "eagle-import") (part "BUS_SPLIT_DISPLAY"))
    )
    (comp (ref "CMP90")
      (value "BUS_SPLIT_DISPLAY")
      (footprint "eagle-import:BUS_SPLIT_DISPLAY")
      (libsource (lib "eagle-import") (part "BUS_SPLIT_DISPLAY"))
    )
    (comp (ref "CMP1")
      (value "DECODER4")
      (footprint "eagle-import:DECODER4")
      (libsource (lib "eagle-import") (part "DECODER4"))
    )
    (comp (ref "CMP83")
      (value "BUS_CONSTRUCT_DISPLAY")
      (footprint "eagle-import:BUS_SPLIT_DISPLAY")
      (libsource (lib "eagle-import") (part "BUS_CONSTRUCT_DISPLAY"))
    )
    (comp (ref "CMP85")
      (value "BUS_CONSTRUCT_DISPLAY")
      (footprint "eagle-import:BUS_SPLIT_DISPLAY")
      (libsource (lib "eagle-import") (part "BUS_CONSTRUCT_DISPLAY"))
    )
    (comp (ref "CMP89")
      (value "BUS_CONSTRUCT_DISPLAY")
      (footprint "eagle-import:BUS_SPLIT_DISPLAY")
      (libsource (lib "eagle-import") (part "BUS_CONSTRUCT_DISPLAY"))
    )
    (comp (ref "CMP3")
      (value "BUS_SPLIT_DISPLAY")
      (footprint "eagle-import:BUS_SPLIT_DISPLAY")
      (libsource (lib "eagle-import") (part "BUS_SPLIT_DISPLAY"))
    )
    (comp (ref "CMP47")
      (value "BUS_SPLIT_DISPLAY")
      (footprint "eagle-import:BUS_SPLIT_DISPLAY")
      (libsource (lib "eagle-import") (part "BUS_SPLIT_DISPLAY"))
    )
    (comp (ref "CMP18")
      (value "2AND")
      (footprint "eagle-import:2AND")
      (libsource (lib "eagle-import") (part "2AND"))
    )
    (comp (ref "CMP19")
      (value "2AND")
      (footprint "eagle-import:2AND")
      (libsource (lib "eagle-import") (part "2AND"))
    )
    (comp (ref "CMP20")
      (value "2AND")
      (footprint "eagle-import:2AND")
      (libsource (lib "eagle-import") (part "2AND"))
    )
    (comp (ref "CMP21")
      (value "2AND")
      (footprint "eagle-import:2AND")
      (libsource (lib "eagle-import") (part "2AND"))
    )
    (comp (ref "CMP41")
      (value "2AND")
      (footprint "eagle-import:2AND")
      (libsource (lib "eagle-import") (part "2AND"))
    )
    (comp (ref "CMP31")
      (value "4X2AND_OR")
      (footprint "eagle-import:4X2AND_OR")
      (libsource (lib "eagle-import") (part "4X2AND_OR"))
    )
    (comp (ref "CMP32")
      (value "2X2AND_OR")
      (footprint "eagle-import:2X2AND_OR")
      (libsource (lib "eagle-import") (part "2X2AND_OR"))
    )
    (comp (ref "CMP33")
      (value "2OR")
      (footprint "eagle-import:2OR")
      (libsource (lib "eagle-import") (part "2OR"))
    )
    (comp (ref "CMP34")
      (value "2X2AND_OR")
      (footprint "eagle-import:2X2AND_OR")
      (libsource (lib "eagle-import") (part "2X2AND_OR"))
    )
    (comp (ref "CMP65")
      (value "2AND")
      (footprint "eagle-import:2AND")
      (libsource (lib "eagle-import") (part "2AND"))
    )
    (comp (ref "CMP66")
      (value "2AND")
      (footprint "eagle-import:2AND")
      (libsource (lib "eagle-import") (part "2AND"))
    )
    (comp (ref "CMP40")
      (value "3OR")
      (footprint "eagle-import:3OR")
      (libsource (lib "eagle-import") (part "3OR"))
    )
    (comp (ref "CMP43")
      (value "3OR")
      (footprint "eagle-import:3OR")
      (libsource (lib "eagle-import") (part "3OR"))
    )
    (comp (ref "CMP44")
      (value "2X2AND_OR")
      (footprint "eagle-import:2X2AND_OR")
      (libsource (lib "eagle-import") (part "2X2AND_OR"))
    )
    (comp (ref "CMP45")
      (value "2X2AND_OR")
      (footprint "eagle-import:2X2AND_OR")
      (libsource (lib "eagle-import") (part "2X2AND_OR"))
    )
  )
  (nets
    (net (code "1") (name "BIT_SHIFT_MODE__CHANGE__ARITH") (class "Default")
      (node (ref "CMP3") (pin "P$7") (pinfunction "OUT_6_P$7") (pintype "output"))
    )
    (net (code "2") (name "BIT_SHIFT_MODE__SET__X_ROT") (class "Default")
      (node (ref "CMP3") (pin "P$8") (pinfunction "OUT_7_P$8") (pintype "output"))
    )
    (net (code "3") (name "BIT_SHIFT_MODE__TEST_N") (class "Default")
      (node (ref "CMP3") (pin "P$6") (pinfunction "OUT_5_P$6") (pintype "output"))
    )
    (net (code "4") (name "BIT_SHIFT_MODE___ROT_N") (class "Default")
      (node (ref "CMP3") (pin "P$9") (pinfunction "OUT_8_P$9") (pintype "output"))
    )
    (net (code "5") (name "BRANCH_NOT_TAKEN") (class "Default")
      (node (ref "CMP85") (pin "P$3") (pinfunction "IN_2_P$3") (pintype "input"))
      (node (ref "CMP88") (pin "OUT_P") (pinfunction "P_OUT_P") (pintype "output"))
    )
    (net (code "6") (name "BRANCH_TAKEN") (class "Default")
      (node (ref "CMP83") (pin "P$10") (pinfunction "IN_9_P$10") (pintype "input"))
      (node (ref "CMP86") (pin "OUT_P") (pinfunction "P_OUT_P") (pintype "output"))
    )
    (net (code "7") (name "BUS_DECODE_SPECIAL_REG_0") (class "Default")
      (node (ref "CMP81") (pin "INPUT") (pinfunction "OUT_INPUT") (pintype "output"))
    )
    (net (code "8") (name "BUS_DECODE_SPECIAL_REG_1") (class "Default")
      (node (ref "CMP58") (pin "INPUT") (pinfunction "OUT_INPUT") (pintype "output"))
    )
    (net (code "9") (name "BUS_DECODE_STATE_1") (class "Default")
      (node (ref "CMP83") (pin "INPUT") (pinfunction "OUT_INPUT") (pintype "output"))
    )
    (net (code "10") (name "BUS_DECODE_STATE_2") (class "Default")
      (node (ref "CMP85") (pin "INPUT") (pinfunction "OUT_INPUT") (pintype "output"))
    )
    (net (code "11") (name "BUS_DECODE_STATE_3") (class "Default")
      (node (ref "CMP89") (pin "INPUT") (pinfunction "OUT_INPUT") (pintype "output"))
    )
    (net (code "12") (name "BUS_INSTR") (class "Default")
      (node (ref "CMP15") (pin "INPUT") (pinfunction "INPUT_INPUT") (pintype "input"))
    )
    (net (code "13") (name "BUS_PS") (class "Default")
      (node (ref "CMP17") (pin "INPUT") (pinfunction "INPUT_INPUT") (pintype "input"))
    )
    (net (code "14") (name "BUS_STATE") (class "Default")
      (node (ref "CMP13") (pin "INPUT") (pinfunction "INPUT_INPUT") (pintype "input"))
    )
    (net (code "15") (name "DIR_SZ_IS_LOAD_BYTE") (class "Default")
      (node (ref "CMP1") (pin "P1") (pinfunction "P1_P1") (pintype "output"))
      (node (ref "CMP85") (pin "P$12") (pinfunction "IN_11_P$12") (pintype "input"))
    )
    (net (code "16") (name "DIR_SZ_IS_LOAD_WORD") (class "Default")
      (node (ref "CMP1") (pin "P0") (pinfunction "P0_P0") (pintype "output"))
      (node (ref "CMP85") (pin "P$9") (pinfunction "IN_8_P$9") (pintype "input"))
    )
    (net (code "17") (name "DIR_SZ_IS_STORE_BYTE") (class "Default")
      (node (ref "CMP1") (pin "P3") (pinfunction "P3_P3") (pintype "output"))
      (node (ref "CMP34") (pin "P$2") (pinfunction "A1_P$2") (pintype "input"))
    )
    (net (code "18") (name "DIR_SZ_IS_STORE_WORD") (class "Default")
      (node (ref "CMP1") (pin "P2") (pinfunction "P2_P2") (pintype "output"))
      (node (ref "CMP32") (pin "P$4") (pinfunction "B1_P$4") (pintype "input"))
    )
    (net (code "19") (name "DIV_BY_ZERO") (class "Default")
      (node (ref "CMP40") (pin "P$3") (pinfunction "2_P$3") (pintype "input"))
      (node (ref "CMP47") (pin "P$12") (pinfunction "OUT_11_P$12") (pintype "output"))
      (node (ref "CMP83") (pin "P$1") (pinfunction "IN_0_P$1") (pintype "input"))
    )
    (net (code "20") (name "DIV_BY_ZERO_N") (class "Default")
      (node (ref "CMP47") (pin "P$13") (pinfunction "OUT_12_P$13") (pintype "output"))
    )
    (net (code "21") (name "DOING_EXCEPTION") (class "Default")
      (node (ref "CMP43") (pin "OUT_P") (pinfunction "P_OUT_P") (pintype "output"))
    )
    (net (code "22") (name "DOING_EXCEPTION_N") (class "Default")
      (node (ref "CMP43") (pin "OUT_M") (pinfunction "N_OUT_M") (pintype "output"))
      (node (ref "CMP44") (pin "P$3") (pinfunction "B0_P$3") (pintype "input"))
      (node (ref "CMP44") (pin "P$4") (pinfunction "B1_P$4") (pintype "input"))
      (node (ref "CMP45") (pin "P$3") (pinfunction "B0_P$3") (pintype "input"))
      (node (ref "CMP45") (pin "P$4") (pinfunction "B1_P$4") (pintype "input"))
    )
    (net (code "23") (name "END_OF_SHIFT") (class "Default")
      (node (ref "CMP85") (pin "P$6") (pinfunction "IN_5_P$6") (pintype "input"))
      (node (ref "CMP98") (pin "OUT_P") (pinfunction "P_OUT_P") (pintype "output"))
    )
    (net (code "24") (name "FLAG_C") (class "Default")
      (node (ref "CMP17") (pin "P$6") (pinfunction "OUT_5_P$6") (pintype "output"))
    )
    (net (code "25") (name "FLAG_D") (class "Default")
      (node (ref "CMP17") (pin "P$7") (pinfunction "OUT_6_P$7") (pintype "output"))
    )
    (net (code "26") (name "FLAG_F0") (class "Default")
      (node (ref "CMP17") (pin "P$9") (pinfunction "OUT_8_P$9") (pintype "output"))
    )
    (net (code "27") (name "FLAG_F1") (class "Default")
      (node (ref "CMP17") (pin "P$10") (pinfunction "OUT_9_P$10") (pintype "output"))
    )
    (net (code "28") (name "FLAG_F2") (class "Default")
      (node (ref "CMP17") (pin "P$11") (pinfunction "OUT_10_P$11") (pintype "output"))
      (node (ref "CMP46") (pin "IN") (pinfunction "IN_IN") (pintype "input"))
    )
    (net (code "29") (name "FLAG_F2_BUF") (class "Default")
      (node (ref "CMP46") (pin "P") (pinfunction "P_P") (pintype "output"))
      (node (ref "CMP85") (pin "P$1") (pinfunction "IN_0_P$1") (pintype "input"))
    )
    (net (code "30") (name "FLAG_F2_N") (class "Default")
      (node (ref "CMP46") (pin "N") (pinfunction "N_N") (pintype "output"))
      (node (ref "CMP58") (pin "P$3") (pinfunction "IN_2_P$3") (pintype "input"))
    )
    (net (code "31") (name "FLAG_F3") (class "Default")
      (node (ref "CMP17") (pin "P$12") (pinfunction "OUT_11_P$12") (pintype "output"))
    )
    (net (code "32") (name "FLAG_F4") (class "Default")
      (node (ref "CMP17") (pin "P$13") (pinfunction "OUT_12_P$13") (pintype "output"))
      (node (ref "CMP43") (pin "P$2") (pinfunction "1_P$2") (pintype "input"))
      (node (ref "CMP44") (pin "P$2") (pinfunction "A1_P$2") (pintype "input"))
    )
    (net (code "33") (name "FLAG_F5") (class "Default")
      (node (ref "CMP17") (pin "P$14") (pinfunction "OUT_13_P$14") (pintype "output"))
      (node (ref "CMP43") (pin "P$1") (pinfunction "0_P$1") (pintype "input"))
      (node (ref "CMP45") (pin "P$1") (pinfunction "A0_P$1") (pintype "input"))
    )
    (net (code "34") (name "FLAG_F6") (class "Default")
      (node (ref "CMP17") (pin "P$15") (pinfunction "OUT_14_P$15") (pintype "output"))
    )
    (net (code "35") (name "FLAG_I") (class "Default")
      (node (ref "CMP17") (pin "P$1") (pinfunction "OUT_0_P$1") (pintype "output"))
    )
    (net (code "36") (name "FLAG_N") (class "Default")
      (node (ref "CMP17") (pin "P$2") (pinfunction "OUT_1_P$2") (pintype "output"))
    )
    (net (code "37") (name "FLAG_V") (class "Default")
      (node (ref "CMP17") (pin "P$4") (pinfunction "OUT_3_P$4") (pintype "output"))
    )
    (net (code "38") (name "FLAG_X") (class "Default")
      (node (ref "CMP17") (pin "P$5") (pinfunction "OUT_4_P$5") (pintype "output"))
    )
    (net (code "39") (name "FLAG_Z") (class "Default")
      (node (ref "CMP17") (pin "P$3") (pinfunction "OUT_2_P$3") (pintype "output"))
    )
    (net (code "40") (name "H_COUNT_IS_15") (class "Default")
      (node (ref "CMP57") (pin "P$3") (pinfunction "OUT_2_P$3") (pintype "output"))
      (node (ref "CMP65") (pin "P$2") (pinfunction "2_P$2") (pintype "input"))
      (node (ref "CMP83") (pin "P$16") (pinfunction "IN_15_P$16") (pintype "input"))
    )
    (net (code "41") (name "INSTR_0") (class "Default")
      (node (ref "CMP15") (pin "P$1") (pinfunction "OUT_0_P$1") (pintype "output"))
      (node (ref "CMP89") (pin "P$3") (pinfunction "IN_2_P$3") (pintype "input"))
    )
    (net (code "42") (name "INSTR_0_N") (class "Default")
      (node (ref "CMP15") (pin "P$9") (pinfunction "OUT_8_P$9") (pintype "output"))
      (node (ref "CMP65") (pin "P$1") (pinfunction "1_P$1") (pintype "input"))
    )
    (net (code "43") (name "INSTR_1") (class "Default")
      (node (ref "CMP15") (pin "P$2") (pinfunction "OUT_1_P$2") (pintype "output"))
    )
    (net (code "44") (name "INSTR_1_N") (class "Default")
      (node (ref "CMP15") (pin "P$10") (pinfunction "OUT_9_P$10") (pintype "output"))
    )
    (net (code "45") (name "INSTR_2") (class "Default")
      (node (ref "CMP1") (pin "A0") (pinfunction "A0_A0") (pintype "input"))
      (node (ref "CMP15") (pin "P$3") (pinfunction "OUT_2_P$3") (pintype "output"))
      (node (ref "CMP81") (pin "P$2") (pinfunction "IN_1_P$2") (pintype "input"))
    )
    (net (code "46") (name "INSTR_2_N") (class "Default")
      (node (ref "CMP15") (pin "P$11") (pinfunction "OUT_10_P$11") (pintype "output"))
      (node (ref "CMP66") (pin "P$2") (pinfunction "2_P$2") (pintype "input"))
    )
    (net (code "47") (name "INSTR_3") (class "Default")
      (node (ref "CMP1") (pin "A1") (pinfunction "A1_A1") (pintype "input"))
      (node (ref "CMP15") (pin "P$4") (pinfunction "OUT_3_P$4") (pintype "output"))
    )
    (net (code "48") (name "INSTR_3_N") (class "Default")
      (node (ref "CMP15") (pin "P$12") (pinfunction "OUT_11_P$12") (pintype "output"))
    )
    (net (code "49") (name "INSTR_4") (class "Default")
      (node (ref "CMP15") (pin "P$5") (pinfunction "OUT_4_P$5") (pintype "output"))
    )
    (net (code "50") (name "INSTR_4_N") (class "Default")
      (node (ref "CMP15") (pin "P$13") (pinfunction "OUT_12_P$13") (pintype "output"))
    )
    (net (code "51") (name "INSTR_5") (class "Default")
      (node (ref "CMP15") (pin "P$6") (pinfunction "OUT_5_P$6") (pintype "output"))
    )
    (net (code "52") (name "INSTR_5_N") (class "Default")
      (node (ref "CMP15") (pin "P$14") (pinfunction "OUT_13_P$14") (pintype "output"))
    )
    (net (code "53") (name "INSTR_6") (class "Default")
      (node (ref "CMP15") (pin "P$7") (pinfunction "OUT_6_P$7") (pintype "output"))
    )
    (net (code "54") (name "INSTR_6_N") (class "Default")
      (node (ref "CMP15") (pin "P$15") (pinfunction "OUT_14_P$15") (pintype "output"))
    )
    (net (code "55") (name "INSTR_7") (class "Default")
      (node (ref "CMP15") (pin "P$8") (pinfunction "OUT_7_P$8") (pintype "output"))
    )
    (net (code "56") (name "INSTR_7_N") (class "Default")
      (node (ref "CMP15") (pin "P$16") (pinfunction "OUT_15_P$16") (pintype "output"))
    )
    (net (code "57") (name "IS_END") (class "Default")
      (node (ref "CMP57") (pin "P$11") (pinfunction "OUT_10_P$11") (pintype "output"))
      (node (ref "CMP58") (pin "P$9") (pinfunction "IN_8_P$9") (pintype "input"))
      (node (ref "CMP83") (pin "P$2") (pinfunction "IN_1_P$2") (pintype "input"))
    )
    (net (code "58") (name "IS_END_N") (class "Default")
      (node (ref "CMP57") (pin "P$12") (pinfunction "OUT_11_P$12") (pintype "output"))
    )
    (net (code "59") (name "IS_NOT_INTERRUPTING_END") (class "Default")
      (node (ref "CMP57") (pin "P$14") (pinfunction "OUT_13_P$14") (pintype "output"))
      (node (ref "CMP58") (pin "P$16") (pinfunction "IN_15_P$16") (pintype "input"))
    )
    (net (code "60") (name "IS_SIMPLE_DATA_TRANSFER") (class "Default")
      (node (ref "CMP31") (pin "P$7") (pinfunction "D0_P$7") (pintype "input"))
      (node (ref "CMP57") (pin "P$13") (pinfunction "OUT_12_P$13") (pintype "output"))
    )
    (net (code "61") (name "LDI_X_STATE_0_BYTE_1_WORD") (class "Default")
      (node (ref "CMP57") (pin "P$9") (pinfunction "OUT_8_P$9") (pintype "output"))
      (node (ref "CMP83") (pin "P$13") (pinfunction "IN_12_P$13") (pintype "input"))
    )
    (net (code "62") (name "LOAD_WEIGHT") (class "Default")
      (node (ref "CMP57") (pin "P$5") (pinfunction "OUT_4_P$5") (pintype "output"))
    )
    (net (code "63") (name "MATCH") (class "Default")
      (node (ref "CMP86") (pin "P$2") (pinfunction "2_P$2") (pintype "input"))
      (node (ref "CMP90") (pin "P$1") (pinfunction "OUT_0_P$1") (pintype "output"))
    )
    (net (code "64") (name "MATCH_N") (class "Default")
      (node (ref "CMP88") (pin "P$2") (pinfunction "2_P$2") (pintype "input"))
      (node (ref "CMP90") (pin "P$2") (pinfunction "OUT_1_P$2") (pintype "output"))
    )
    (net (code "65") (name "Net-(CMP31-A0)") (class "Default")
      (node (ref "CMP31") (pin "P$1") (pinfunction "A0_P$1") (pintype "input"))
      (node (ref "CMP31") (pin "P$2") (pinfunction "A1_P$2") (pintype "input"))
    )
    (net (code "66") (name "Net-(CMP89-IN_10)") (class "Default")
      (node (ref "CMP89") (pin "P$10") (pinfunction "IN_9_P$10") (pintype "input"))
      (node (ref "CMP89") (pin "P$11") (pinfunction "IN_10_P$11") (pintype "input"))
      (node (ref "CMP89") (pin "P$12") (pinfunction "IN_11_P$12") (pintype "input"))
      (node (ref "CMP89") (pin "P$13") (pinfunction "IN_12_P$13") (pintype "input"))
      (node (ref "CMP89") (pin "P$14") (pinfunction "IN_13_P$14") (pintype "input"))
      (node (ref "CMP89") (pin "P$15") (pinfunction "IN_14_P$15") (pintype "input"))
      (node (ref "CMP89") (pin "P$16") (pinfunction "IN_15_P$16") (pintype "input"))
      (node (ref "CMP89") (pin "P$6") (pinfunction "IN_5_P$6") (pintype "input"))
      (node (ref "CMP89") (pin "P$7") (pinfunction "IN_6_P$7") (pintype "input"))
      (node (ref "CMP89") (pin "P$8") (pinfunction "IN_7_P$8") (pintype "input"))
      (node (ref "CMP89") (pin "P$9") (pinfunction "IN_8_P$9") (pintype "input"))
    )
    (net (code "67") (name "OPCODE_IS_ABS") (class "Default")
      (node (ref "CMP47") (pin "P$4") (pinfunction "OUT_3_P$4") (pintype "output"))
    )
    (net (code "68") (name "OPCODE_IS_ABSOLUTE_GROUP") (class "Default")
      (node (ref "CMP2") (pin "P$5") (pinfunction "OUT_4_P$5") (pintype "output"))
      (node (ref "CMP31") (pin "P$6") (pinfunction "C1_P$6") (pintype "input"))
      (node (ref "CMP81") (pin "P$12") (pinfunction "IN_11_P$12") (pintype "input"))
      (node (ref "CMP83") (pin "P$6") (pinfunction "IN_5_P$6") (pintype "input"))
    )
    (net (code "69") (name "OPCODE_IS_ADDQ_GROUP") (class "Default")
      (node (ref "CMP2") (pin "P$11") (pinfunction "OUT_10_P$11") (pintype "output"))
    )
    (net (code "70") (name "OPCODE_IS_ADDX") (class "Default")
      (node (ref "CMP35") (pin "P$3") (pinfunction "OUT_2_P$3") (pintype "output"))
    )
    (net (code "71") (name "OPCODE_IS_ADD_GROUP") (class "Default")
      (node (ref "CMP2") (pin "P$12") (pinfunction "OUT_11_P$12") (pintype "output"))
    )
    (net (code "72") (name "OPCODE_IS_ADD_SP") (class "Default")
      (node (ref "CMP18") (pin "P$2") (pinfunction "2_P$2") (pintype "input"))
      (node (ref "CMP35") (pin "P$10") (pinfunction "OUT_9_P$10") (pintype "output"))
      (node (ref "CMP58") (pin "P$7") (pinfunction "IN_6_P$7") (pintype "input"))
      (node (ref "CMP83") (pin "P$11") (pinfunction "IN_10_P$11") (pintype "input"))
    )
    (net (code "73") (name "OPCODE_IS_ADD_SP_STATE_2") (class "Default")
      (node (ref "CMP18") (pin "OUT_P") (pinfunction "P_OUT_P") (pintype "output"))
      (node (ref "CMP83") (pin "P$14") (pinfunction "IN_13_P$14") (pintype "input"))
    )
    (net (code "74") (name "OPCODE_IS_ANDI_ORI_PS") (class "Default")
      (node (ref "CMP25") (pin "OUT_P") (pinfunction "P_OUT_P") (pintype "output"))
      (node (ref "CMP85") (pin "P$4") (pinfunction "IN_3_P$4") (pintype "input"))
    )
    (net (code "75") (name "OPCODE_IS_ANDI_ORI_PS_LDI_X") (class "Default")
      (node (ref "CMP104") (pin "OUT_P") (pinfunction "P_OUT_P") (pintype "output"))
      (node (ref "CMP58") (pin "P$8") (pinfunction "IN_7_P$8") (pintype "input"))
    )
    (net (code "76") (name "OPCODE_IS_ANDI_PS") (class "Default")
      (node (ref "CMP104") (pin "P$2") (pinfunction "1_P$2") (pintype "input"))
      (node (ref "CMP25") (pin "P$2") (pinfunction "A1_P$2") (pintype "input"))
      (node (ref "CMP35") (pin "P$12") (pinfunction "OUT_11_P$12") (pintype "output"))
    )
    (net (code "77") (name "OPCODE_IS_AND_GROUP") (class "Default")
      (node (ref "CMP2") (pin "P$15") (pinfunction "OUT_14_P$15") (pintype "output"))
    )
    (net (code "78") (name "OPCODE_IS_BIT_XX") (class "Default")
      (node (ref "CMP3") (pin "P$3") (pinfunction "OUT_2_P$3") (pintype "output"))
      (node (ref "CMP83") (pin "P$4") (pinfunction "IN_3_P$4") (pintype "input"))
    )
    (net (code "79") (name "OPCODE_IS_BIT_XX_N") (class "Default")
      (node (ref "CMP3") (pin "P$4") (pinfunction "OUT_3_P$4") (pintype "output"))
    )
    (net (code "80") (name "OPCODE_IS_BRANCH_GROUP") (class "Default")
      (node (ref "CMP19") (pin "P$2") (pinfunction "2_P$2") (pintype "input"))
      (node (ref "CMP2") (pin "P$3") (pinfunction "OUT_2_P$3") (pintype "output"))
      (node (ref "CMP58") (pin "P$6") (pinfunction "IN_5_P$6") (pintype "input"))
      (node (ref "CMP85") (pin "P$7") (pinfunction "IN_6_P$7") (pintype "input"))
      (node (ref "CMP88") (pin "P$1") (pinfunction "1_P$1") (pintype "input"))
    )
    (net (code "81") (name "OPCODE_IS_BXX_STATE_2") (class "Default")
      (node (ref "CMP19") (pin "OUT_P") (pinfunction "P_OUT_P") (pintype "output"))
      (node (ref "CMP58") (pin "P$12") (pinfunction "IN_11_P$12") (pintype "input"))
    )
    (net (code "82") (name "OPCODE_IS_CMP") (class "Default")
      (node (ref "CMP47") (pin "P$3") (pinfunction "OUT_2_P$3") (pintype "output"))
    )
    (net (code "83") (name "OPCODE_IS_CMP_GROUP") (class "Default")
      (node (ref "CMP2") (pin "P$9") (pinfunction "OUT_8_P$9") (pintype "output"))
    )
    (net (code "84") (name "OPCODE_IS_DIV") (class "Default")
      (node (ref "CMP35") (pin "P$4") (pinfunction "OUT_3_P$4") (pintype "output"))
      (node (ref "CMP41") (pin "P$2") (pinfunction "2_P$2") (pintype "input"))
    )
    (net (code "85") (name "OPCODE_IS_DIVS") (class "Default")
      (node (ref "CMP35") (pin "P$5") (pinfunction "OUT_4_P$5") (pintype "output"))
    )
    (net (code "86") (name "OPCODE_IS_DIV_STATE_0") (class "Default")
      (node (ref "CMP41") (pin "OUT_P") (pinfunction "P_OUT_P") (pintype "output"))
      (node (ref "CMP89") (pin "P$2") (pinfunction "IN_1_P$2") (pintype "input"))
    )
    (net (code "87") (name "OPCODE_IS_INDIRECT_GROUP") (class "Default")
      (node (ref "CMP2") (pin "P$8") (pinfunction "OUT_7_P$8") (pintype "output"))
    )
    (net (code "88") (name "OPCODE_IS_INDIRECT_POSTINC") (class "Default")
      (node (ref "CMP2") (pin "P$1") (pinfunction "OUT_0_P$1") (pintype "output"))
      (node (ref "CMP81") (pin "P$3") (pinfunction "IN_2_P$3") (pintype "input"))
    )
    (net (code "89") (name "OPCODE_IS_INV") (class "Default")
      (node (ref "CMP47") (pin "P$8") (pinfunction "OUT_7_P$8") (pintype "output"))
    )
    (net (code "90") (name "OPCODE_IS_JMP_ABS") (class "Default")
      (node (ref "CMP35") (pin "P$13") (pinfunction "OUT_12_P$13") (pintype "output"))
      (node (ref "CMP58") (pin "P$10") (pinfunction "IN_9_P$10") (pintype "input"))
      (node (ref "CMP83") (pin "P$5") (pinfunction "IN_4_P$5") (pintype "input"))
    )
    (net (code "91") (name "OPCODE_IS_JMP_R0") (class "Default")
      (node (ref "CMP35") (pin "P$14") (pinfunction "OUT_13_P$14") (pintype "output"))
      (node (ref "CMP58") (pin "P$5") (pinfunction "IN_4_P$5") (pintype "input"))
      (node (ref "CMP85") (pin "P$2") (pinfunction "IN_1_P$2") (pintype "input"))
    )
    (net (code "92") (name "OPCODE_IS_JSR_ABS") (class "Default")
      (node (ref "CMP3") (pin "P$10") (pinfunction "OUT_9_P$10") (pintype "output"))
      (node (ref "CMP81") (pin "P$6") (pinfunction "IN_5_P$6") (pintype "input"))
      (node (ref "CMP83") (pin "P$7") (pinfunction "IN_6_P$7") (pintype "input"))
    )
    (net (code "93") (name "OPCODE_IS_JSR_R0") (class "Default")
      (node (ref "CMP3") (pin "P$11") (pinfunction "OUT_10_P$11") (pintype "output"))
      (node (ref "CMP32") (pin "P$2") (pinfunction "A1_P$2") (pintype "input"))
      (node (ref "CMP81") (pin "P$5") (pinfunction "IN_4_P$5") (pintype "input"))
    )
    (net (code "94") (name "OPCODE_IS_JSR_X") (class "Default")
      (node (ref "CMP21") (pin "P$1") (pinfunction "1_P$1") (pintype "input"))
      (node (ref "CMP57") (pin "P$10") (pinfunction "OUT_9_P$10") (pintype "output"))
    )
    (net (code "95") (name "OPCODE_IS_JSR_X_STATE_7") (class "Default")
      (node (ref "CMP21") (pin "OUT_P") (pinfunction "P_OUT_P") (pintype "output"))
      (node (ref "CMP58") (pin "P$4") (pinfunction "IN_3_P$4") (pintype "input"))
      (node (ref "CMP83") (pin "P$15") (pinfunction "IN_14_P$15") (pintype "input"))
    )
    (net (code "96") (name "OPCODE_IS_LDI_X") (class "Default")
      (node (ref "CMP104") (pin "P$1") (pinfunction "0_P$1") (pintype "input"))
      (node (ref "CMP3") (pin "P$1") (pinfunction "OUT_0_P$1") (pintype "output"))
      (node (ref "CMP66") (pin "P$1") (pinfunction "1_P$1") (pintype "input"))
    )
    (net (code "97") (name "OPCODE_IS_LD_ST") (class "Default")
      (node (ref "CMP57") (pin "P$8") (pinfunction "OUT_7_P$8") (pintype "output"))
    )
    (net (code "98") (name "OPCODE_IS_LOGIC_GROUP") (class "Default")
      (node (ref "CMP2") (pin "P$2") (pinfunction "OUT_1_P$2") (pintype "output"))
    )
    (net (code "99") (name "OPCODE_IS_MOVER") (class "Default")
      (node (ref "CMP47") (pin "P$10") (pinfunction "OUT_9_P$10") (pintype "output"))
    )
    (net (code "100") (name "OPCODE_IS_MOVER_SP") (class "Default")
      (node (ref "CMP26") (pin "OUT_P") (pinfunction "P_OUT_P") (pintype "output"))
      (node (ref "CMP85") (pin "P$5") (pinfunction "IN_4_P$5") (pintype "input"))
    )
    (net (code "101") (name "OPCODE_IS_MOVE_R0_SP") (class "Default")
      (node (ref "CMP26") (pin "P$1") (pinfunction "A2_P$1") (pintype "input"))
      (node (ref "CMP35") (pin "P$16") (pinfunction "OUT_15_P$16") (pintype "output"))
    )
    (net (code "102") (name "OPCODE_IS_MOVE_SP_R0") (class "Default")
      (node (ref "CMP26") (pin "P$2") (pinfunction "A1_P$2") (pintype "input"))
      (node (ref "CMP35") (pin "P$15") (pinfunction "OUT_14_P$15") (pintype "output"))
      (node (ref "CMP58") (pin "P$2") (pinfunction "IN_1_P$2") (pintype "input"))
    )
    (net (code "103") (name "OPCODE_IS_MUL") (class "Default")
      (node (ref "CMP35") (pin "P$7") (pinfunction "OUT_6_P$7") (pintype "output"))
      (node (ref "CMP89") (pin "P$4") (pinfunction "IN_3_P$4") (pintype "input"))
    )
    (net (code "104") (name "OPCODE_IS_MULS") (class "Default")
      (node (ref "CMP35") (pin "P$8") (pinfunction "OUT_7_P$8") (pintype "output"))
    )
    (net (code "105") (name "OPCODE_IS_MUL_N") (class "Default")
      (node (ref "CMP35") (pin "P$6") (pinfunction "OUT_5_P$6") (pintype "output"))
    )
    (net (code "106") (name "OPCODE_IS_MUL_SQRT_DIV") (class "Default")
      (node (ref "CMP47") (pin "P$1") (pinfunction "OUT_0_P$1") (pintype "output"))
      (node (ref "CMP58") (pin "P$15") (pinfunction "IN_14_P$15") (pintype "input"))
    )
    (net (code "107") (name "OPCODE_IS_NEG") (class "Default")
      (node (ref "CMP47") (pin "P$6") (pinfunction "OUT_5_P$6") (pintype "output"))
    )
    (net (code "108") (name "OPCODE_IS_NEGX") (class "Default")
      (node (ref "CMP35") (pin "P$1") (pinfunction "OUT_0_P$1") (pintype "output"))
    )
    (net (code "109") (name "OPCODE_IS_OR") (class "Default")
      (node (ref "CMP47") (pin "P$7") (pinfunction "OUT_6_P$7") (pintype "output"))
    )
    (net (code "110") (name "OPCODE_IS_ORI_PS") (class "Default")
      (node (ref "CMP104") (pin "P$3") (pinfunction "2_P$3") (pintype "input"))
      (node (ref "CMP25") (pin "P$1") (pinfunction "A2_P$1") (pintype "input"))
      (node (ref "CMP35") (pin "P$11") (pinfunction "OUT_10_P$11") (pintype "output"))
    )
    (net (code "111") (name "OPCODE_IS_OR_GROUP") (class "Default")
      (node (ref "CMP2") (pin "P$13") (pinfunction "OUT_12_P$13") (pintype "output"))
    )
    (net (code "112") (name "OPCODE_IS_POP_PS") (class "Default")
      (node (ref "CMP3") (pin "P$16") (pinfunction "OUT_15_P$16") (pintype "output"))
      (node (ref "CMP92") (pin "P$1") (pinfunction "A2_P$1") (pintype "input"))
    )
    (net (code "113") (name "OPCODE_IS_POP_RA") (class "Default")
      (node (ref "CMP47") (pin "P$15") (pinfunction "OUT_14_P$15") (pintype "output"))
      (node (ref "CMP92") (pin "P$2") (pinfunction "A1_P$2") (pintype "input"))
    )
    (net (code "114") (name "OPCODE_IS_POP_RA_PS") (class "Default")
      (node (ref "CMP81") (pin "P$14") (pinfunction "IN_13_P$14") (pintype "input"))
      (node (ref "CMP92") (pin "OUT_P") (pinfunction "P_OUT_P") (pintype "output"))
    )
    (net (code "115") (name "OPCODE_IS_POSTINC_GROUP") (class "Default")
      (node (ref "CMP2") (pin "P$7") (pinfunction "OUT_6_P$7") (pintype "output"))
    )
    (net (code "116") (name "OPCODE_IS_PUSH_PS") (class "Default")
      (node (ref "CMP3") (pin "P$13") (pinfunction "OUT_12_P$13") (pintype "output"))
      (node (ref "CMP81") (pin "P$9") (pinfunction "IN_8_P$9") (pintype "input"))
    )
    (net (code "117") (name "OPCODE_IS_PUSH_RA") (class "Default")
      (node (ref "CMP47") (pin "P$16") (pinfunction "OUT_15_P$16") (pintype "output"))
      (node (ref "CMP81") (pin "P$1") (pinfunction "IN_0_P$1") (pintype "input"))
    )
    (net (code "118") (name "OPCODE_IS_RET") (class "Default")
      (node (ref "CMP3") (pin "P$15") (pinfunction "OUT_14_P$15") (pintype "output"))
      (node (ref "CMP73") (pin "P$1") (pinfunction "A2_P$1") (pintype "input"))
      (node (ref "CMP85") (pin "P$11") (pinfunction "IN_10_P$11") (pintype "input"))
    )
    (net (code "119") (name "OPCODE_IS_RETI") (class "Default")
      (node (ref "CMP3") (pin "P$14") (pinfunction "OUT_13_P$14") (pintype "output"))
      (node (ref "CMP73") (pin "P$2") (pinfunction "A1_P$2") (pintype "input"))
      (node (ref "CMP85") (pin "P$15") (pinfunction "IN_14_P$15") (pintype "input"))
    )
    (net (code "120") (name "OPCODE_IS_RET_RETI") (class "Default")
      (node (ref "CMP58") (pin "P$11") (pinfunction "IN_10_P$11") (pintype "input"))
      (node (ref "CMP73") (pin "OUT_P") (pinfunction "P_OUT_P") (pintype "output"))
    )
    (net (code "121") (name "OPCODE_IS_SHIFT_BIT") (class "Default")
      (node (ref "CMP3") (pin "P$5") (pinfunction "OUT_4_P$5") (pintype "output"))
      (node (ref "CMP81") (pin "P$10") (pinfunction "IN_9_P$10") (pintype "input"))
    )
    (net (code "122") (name "OPCODE_IS_SHIFT_XX") (class "Default")
      (node (ref "CMP3") (pin "P$2") (pinfunction "OUT_1_P$2") (pintype "output"))
      (node (ref "CMP81") (pin "P$16") (pinfunction "IN_15_P$16") (pintype "input"))
      (node (ref "CMP83") (pin "P$3") (pinfunction "IN_2_P$3") (pintype "input"))
      (node (ref "CMP98") (pin "P$2") (pinfunction "2_P$2") (pintype "input"))
    )
    (net (code "123") (name "OPCODE_IS_SQRT") (class "Default")
      (node (ref "CMP35") (pin "P$9") (pinfunction "OUT_8_P$9") (pintype "output"))
      (node (ref "CMP89") (pin "P$1") (pinfunction "IN_0_P$1") (pintype "input"))
    )
    (net (code "124") (name "OPCODE_IS_STACK_GROUP") (class "Default")
      (node (ref "CMP2") (pin "P$4") (pinfunction "OUT_3_P$4") (pintype "output"))
      (node (ref "CMP58") (pin "P$1") (pinfunction "IN_0_P$1") (pintype "input"))
    )
    (net (code "125") (name "OPCODE_IS_STACK_REL_GROUP") (class "Default")
      (node (ref "CMP2") (pin "P$6") (pinfunction "OUT_5_P$6") (pintype "output"))
      (node (ref "CMP20") (pin "P$2") (pinfunction "2_P$2") (pintype "input"))
      (node (ref "CMP81") (pin "P$11") (pinfunction "IN_10_P$11") (pintype "input"))
      (node (ref "CMP83") (pin "P$9") (pinfunction "IN_8_P$9") (pintype "input"))
    )
    (net (code "126") (name "OPCODE_IS_STACK_REL_STATE_2") (class "Default")
      (node (ref "CMP20") (pin "OUT_P") (pinfunction "P_OUT_P") (pintype "output"))
      (node (ref "CMP31") (pin "P$3") (pinfunction "B0_P$3") (pintype "input"))
      (node (ref "CMP31") (pin "P$4") (pinfunction "B1_P$4") (pintype "input"))
      (node (ref "CMP81") (pin "P$15") (pinfunction "IN_14_P$15") (pintype "input"))
    )
    (net (code "127") (name "OPCODE_IS_SUB") (class "Default")
      (node (ref "CMP47") (pin "P$5") (pinfunction "OUT_4_P$5") (pintype "output"))
    )
    (net (code "128") (name "OPCODE_IS_SUBX") (class "Default")
      (node (ref "CMP35") (pin "P$2") (pinfunction "OUT_1_P$2") (pintype "output"))
    )
    (net (code "129") (name "OPCODE_IS_SUB_GROUP") (class "Default")
      (node (ref "CMP2") (pin "P$10") (pinfunction "OUT_9_P$10") (pintype "output"))
    )
    (net (code "130") (name "OPCODE_IS_SXT") (class "Default")
      (node (ref "CMP47") (pin "P$11") (pinfunction "OUT_10_P$11") (pintype "output"))
    )
    (net (code "131") (name "OPCODE_IS_TEST") (class "Default")
      (node (ref "CMP47") (pin "P$9") (pinfunction "OUT_8_P$9") (pintype "output"))
    )
    (net (code "132") (name "OPCODE_IS_TRAP") (class "Default")
      (node (ref "CMP3") (pin "P$12") (pinfunction "OUT_11_P$12") (pintype "output"))
      (node (ref "CMP81") (pin "P$8") (pinfunction "IN_7_P$8") (pintype "input"))
      (node (ref "CMP89") (pin "P$5") (pinfunction "IN_4_P$5") (pintype "input"))
    )
    (net (code "133") (name "OPCODE_IS_XOR_GROUP") (class "Default")
      (node (ref "CMP2") (pin "P$14") (pinfunction "OUT_13_P$14") (pintype "output"))
    )
    (net (code "134") (name "OPCODE_IS_X_ARITH") (class "Default")
      (node (ref "CMP47") (pin "P$2") (pinfunction "OUT_1_P$2") (pintype "output"))
    )
    (net (code "135") (name "RESET_SIGNAL") (class "Default")
      (node (ref "CMP4") (pin "IN") (pinfunction "IN_IN") (pintype "input"))
      (node (ref "CMP40") (pin "P$1") (pinfunction "0_P$1") (pintype "input"))
      (node (ref "CMP43") (pin "P$3") (pinfunction "2_P$3") (pintype "input"))
    )
    (net (code "136") (name "RESET_SIGNAL_N") (class "Default")
      (node (ref "CMP4") (pin "N") (pinfunction "N_N") (pintype "output"))
      (node (ref "CMP44") (pin "P$1") (pinfunction "A0_P$1") (pintype "input"))
      (node (ref "CMP45") (pin "P$2") (pinfunction "A1_P$2") (pintype "input"))
    )
    (net (code "137") (name "SHIFT_IS_SHIFTING") (class "Default")
      (node (ref "CMP57") (pin "P$4") (pinfunction "OUT_3_P$4") (pintype "output"))
      (node (ref "CMP83") (pin "P$12") (pinfunction "IN_11_P$12") (pintype "input"))
    )
    (net (code "138") (name "SHIFT_VAL_NON_ZERO") (class "Default")
      (node (ref "CMP57") (pin "P$1") (pinfunction "OUT_0_P$1") (pintype "output"))
    )
    (net (code "139") (name "SHIFT_VAL_NON_ZERO_N") (class "Default")
      (node (ref "CMP57") (pin "P$2") (pinfunction "OUT_1_P$2") (pintype "output"))
      (node (ref "CMP98") (pin "P$1") (pinfunction "1_P$1") (pintype "input"))
    )
    (net (code "140") (name "START_TRANSFER_CYCLE") (class "Default")
      (node (ref "CMP31") (pin "OUT_P") (pinfunction "P_OUT_P") (pintype "output"))
      (node (ref "CMP32") (pin "P$3") (pinfunction "B0_P$3") (pintype "input"))
      (node (ref "CMP34") (pin "P$1") (pinfunction "A0_P$1") (pintype "input"))
      (node (ref "CMP85") (pin "P$10") (pinfunction "IN_9_P$10") (pintype "input"))
    )
    (net (code "141") (name "STATE_0") (class "Default")
      (node (ref "CMP13") (pin "P$1") (pinfunction "OUT_0_P$1") (pintype "output"))
      (node (ref "CMP31") (pin "P$8") (pinfunction "D1_P$8") (pintype "input"))
      (node (ref "CMP32") (pin "P$1") (pinfunction "A0_P$1") (pintype "input"))
      (node (ref "CMP41") (pin "P$1") (pinfunction "1_P$1") (pintype "input"))
      (node (ref "CMP86") (pin "P$1") (pinfunction "1_P$1") (pintype "input"))
    )
    (net (code "142") (name "STATE_1") (class "Default")
      (node (ref "CMP13") (pin "P$2") (pinfunction "OUT_1_P$2") (pintype "output"))
      (node (ref "CMP31") (pin "P$5") (pinfunction "C0_P$5") (pintype "input"))
    )
    (net (code "143") (name "STATE_2") (class "Default")
      (node (ref "CMP13") (pin "P$3") (pinfunction "OUT_2_P$3") (pintype "output"))
      (node (ref "CMP18") (pin "P$1") (pinfunction "1_P$1") (pintype "input"))
      (node (ref "CMP19") (pin "P$1") (pinfunction "1_P$1") (pintype "input"))
      (node (ref "CMP20") (pin "P$1") (pinfunction "1_P$1") (pintype "input"))
    )
    (net (code "144") (name "STATE_3") (class "Default")
      (node (ref "CMP13") (pin "P$4") (pinfunction "OUT_3_P$4") (pintype "output"))
    )
    (net (code "145") (name "STATE_4") (class "Default")
      (node (ref "CMP13") (pin "P$5") (pinfunction "OUT_4_P$5") (pintype "output"))
    )
    (net (code "146") (name "STATE_5") (class "Default")
      (node (ref "CMP13") (pin "P$6") (pinfunction "OUT_5_P$6") (pintype "output"))
    )
    (net (code "147") (name "STATE_6") (class "Default")
      (node (ref "CMP13") (pin "P$7") (pinfunction "OUT_6_P$7") (pintype "output"))
      (node (ref "CMP34") (pin "P$3") (pinfunction "B0_P$3") (pintype "input"))
      (node (ref "CMP34") (pin "P$4") (pinfunction "B1_P$4") (pintype "input"))
    )
    (net (code "148") (name "STATE_7") (class "Default")
      (node (ref "CMP13") (pin "P$8") (pinfunction "OUT_7_P$8") (pintype "output"))
      (node (ref "CMP21") (pin "P$2") (pinfunction "2_P$2") (pintype "input"))
    )
    (net (code "149") (name "STATE_8") (class "Default")
      (node (ref "CMP13") (pin "P$9") (pinfunction "OUT_8_P$9") (pintype "output"))
    )
    (net (code "150") (name "STATE_9") (class "Default")
      (node (ref "CMP13") (pin "P$10") (pinfunction "OUT_9_P$10") (pintype "output"))
    )
    (net (code "151") (name "STATE_10") (class "Default")
      (node (ref "CMP13") (pin "P$11") (pinfunction "OUT_10_P$11") (pintype "output"))
    )
    (net (code "152") (name "STATE_11") (class "Default")
      (node (ref "CMP13") (pin "P$12") (pinfunction "OUT_11_P$12") (pintype "output"))
    )
    (net (code "153") (name "STATE_12") (class "Default")
      (node (ref "CMP13") (pin "P$13") (pinfunction "OUT_12_P$13") (pintype "output"))
    )
    (net (code "154") (name "STATE_13") (class "Default")
      (node (ref "CMP13") (pin "P$14") (pinfunction "OUT_13_P$14") (pintype "output"))
    )
    (net (code "155") (name "STATE_14") (class "Default")
      (node (ref "CMP13") (pin "P$15") (pinfunction "OUT_14_P$15") (pintype "output"))
    )
    (net (code "156") (name "STATE_15") (class "Default")
      (node (ref "CMP13") (pin "P$16") (pinfunction "OUT_15_P$16") (pintype "output"))
      (node (ref "CMP33") (pin "P$1") (pinfunction "A2_P$1") (pintype "input"))
    )
    (net (code "157") (name "TAKE_EXCEPTION") (class "Default")
      (node (ref "CMP40") (pin "OUT_P") (pinfunction "P_OUT_P") (pintype "output"))
      (node (ref "CMP81") (pin "P$13") (pinfunction "IN_12_P$13") (pintype "input"))
    )
    (net (code "158") (name "TAKE_INTERRUPT") (class "Default")
      (node (ref "CMP40") (pin "P$2") (pinfunction "1_P$2") (pintype "input"))
      (node (ref "CMP57") (pin "P$7") (pinfunction "OUT_6_P$7") (pintype "output"))
    )
    (net (code "159") (name "TRAP_STATE_7") (class "Default")
      (node (ref "CMP57") (pin "P$6") (pinfunction "OUT_5_P$6") (pintype "output"))
      (node (ref "CMP85") (pin "P$16") (pinfunction "IN_15_P$16") (pintype "input"))
    )
    (net (code "160") (name "UNSIGNED_15") (class "Default")
      (node (ref "CMP65") (pin "OUT_P") (pinfunction "P_OUT_P") (pintype "output"))
      (node (ref "CMP85") (pin "P$8") (pinfunction "IN_7_P$8") (pintype "input"))
    )
    (net (code "161") (name "VECTOR_CODE_0") (class "Default")
      (node (ref "CMP44") (pin "OUT_P") (pinfunction "P_OUT_P") (pintype "output"))
      (node (ref "CMP58") (pin "P$13") (pinfunction "IN_12_P$13") (pintype "input"))
    )
    (net (code "162") (name "VECTOR_CODE_1") (class "Default")
      (node (ref "CMP45") (pin "OUT_P") (pinfunction "P_OUT_P") (pintype "output"))
      (node (ref "CMP58") (pin "P$14") (pinfunction "IN_13_P$14") (pintype "input"))
    )
    (net (code "163") (name "WILL_BE_1__LDI") (class "Default")
      (node (ref "CMP66") (pin "OUT_P") (pinfunction "P_OUT_P") (pintype "output"))
      (node (ref "CMP83") (pin "P$8") (pinfunction "IN_7_P$8") (pintype "input"))
    )
    (net (code "164") (name "WILL_BE_6__SET_A") (class "Default")
      (node (ref "CMP32") (pin "OUT_P") (pinfunction "P_OUT_P") (pintype "output"))
      (node (ref "CMP33") (pin "P$2") (pinfunction "A1_P$2") (pintype "input"))
    )
    (net (code "165") (name "WILL_BE_STATE_6") (class "Default")
      (node (ref "CMP33") (pin "OUT_P") (pinfunction "P_OUT_P") (pintype "output"))
      (node (ref "CMP81") (pin "P$7") (pinfunction "IN_6_P$7") (pintype "input"))
      (node (ref "CMP85") (pin "P$13") (pinfunction "IN_12_P$13") (pintype "input"))
    )
    (net (code "166") (name "WILL_BE_STATE_7") (class "Default")
      (node (ref "CMP34") (pin "OUT_P") (pinfunction "P_OUT_P") (pintype "output"))
      (node (ref "CMP81") (pin "P$4") (pinfunction "IN_3_P$4") (pintype "input"))
      (node (ref "CMP85") (pin "P$14") (pinfunction "IN_13_P$14") (pintype "input"))
    )
    (net (code "167") (name "unconnected-(CMP1-PadE)") (class "Default")
      (node (ref "CMP1") (pin "E") (pinfunction "E_E") (pintype "input"))
    )
    (net (code "168") (name "unconnected-(CMP1-PadN0)") (class "Default")
      (node (ref "CMP1") (pin "N0") (pinfunction "N0_N0") (pintype "output"))
    )
    (net (code "169") (name "unconnected-(CMP1-PadN1)") (class "Default")
      (node (ref "CMP1") (pin "N1") (pinfunction "N1_N1") (pintype "output"))
    )
    (net (code "170") (name "unconnected-(CMP1-PadN2)") (class "Default")
      (node (ref "CMP1") (pin "N2") (pinfunction "N2_N2") (pintype "output"))
    )
    (net (code "171") (name "unconnected-(CMP1-PadN3)") (class "Default")
      (node (ref "CMP1") (pin "N3") (pinfunction "N3_N3") (pintype "output"))
    )
    (net (code "172") (name "unconnected-(CMP2-OUT_15-PadP$16)") (class "Default")
      (node (ref "CMP2") (pin "P$16") (pinfunction "OUT_15_P$16") (pintype "output"))
    )
    (net (code "173") (name "unconnected-(CMP2-PadINPUT)") (class "Default")
      (node (ref "CMP2") (pin "INPUT") (pinfunction "INPUT_INPUT") (pintype "input"))
    )
    (net (code "174") (name "unconnected-(CMP3-PadINPUT)") (class "Default")
      (node (ref "CMP3") (pin "INPUT") (pinfunction "INPUT_INPUT") (pintype "input"))
    )
    (net (code "175") (name "unconnected-(CMP4-PadP)") (class "Default")
      (node (ref "CMP4") (pin "P") (pinfunction "P_P") (pintype "output"))
    )
    (net (code "176") (name "unconnected-(CMP17-OUT_7-PadP$8)") (class "Default")
      (node (ref "CMP17") (pin "P$8") (pinfunction "OUT_7_P$8") (pintype "output"))
    )
    (net (code "177") (name "unconnected-(CMP17-OUT_15-PadP$16)") (class "Default")
      (node (ref "CMP17") (pin "P$16") (pinfunction "OUT_15_P$16") (pintype "output"))
    )
    (net (code "178") (name "unconnected-(CMP18-N-PadOUT_M)") (class "Default")
      (node (ref "CMP18") (pin "OUT_M") (pinfunction "N_OUT_M") (pintype "output"))
    )
    (net (code "179") (name "unconnected-(CMP19-N-PadOUT_M)") (class "Default")
      (node (ref "CMP19") (pin "OUT_M") (pinfunction "N_OUT_M") (pintype "output"))
    )
    (net (code "180") (name "unconnected-(CMP20-N-PadOUT_M)") (class "Default")
      (node (ref "CMP20") (pin "OUT_M") (pinfunction "N_OUT_M") (pintype "output"))
    )
    (net (code "181") (name "unconnected-(CMP21-N-PadOUT_M)") (class "Default")
      (node (ref "CMP21") (pin "OUT_M") (pinfunction "N_OUT_M") (pintype "output"))
    )
    (net (code "182") (name "unconnected-(CMP25-N-PadOUT_M)") (class "Default")
      (node (ref "CMP25") (pin "OUT_M") (pinfunction "N_OUT_M") (pintype "output"))
    )
    (net (code "183") (name "unconnected-(CMP26-N-PadOUT_M)") (class "Default")
      (node (ref "CMP26") (pin "OUT_M") (pinfunction "N_OUT_M") (pintype "output"))
    )
    (net (code "184") (name "unconnected-(CMP31-N-PadOUT_M)") (class "Default")
      (node (ref "CMP31") (pin "OUT_M") (pinfunction "N_OUT_M") (pintype "output"))
    )
    (net (code "185") (name "unconnected-(CMP32-N-PadOUT_M)") (class "Default")
      (node (ref "CMP32") (pin "OUT_M") (pinfunction "N_OUT_M") (pintype "output"))
    )
    (net (code "186") (name "unconnected-(CMP33-N-PadOUT_M)") (class "Default")
      (node (ref "CMP33") (pin "OUT_M") (pinfunction "N_OUT_M") (pintype "output"))
    )
    (net (code "187") (name "unconnected-(CMP34-N-PadOUT_M)") (class "Default")
      (node (ref "CMP34") (pin "OUT_M") (pinfunction "N_OUT_M") (pintype "output"))
    )
    (net (code "188") (name "unconnected-(CMP35-PadINPUT)") (class "Default")
      (node (ref "CMP35") (pin "INPUT") (pinfunction "INPUT_INPUT") (pintype "input"))
    )
    (net (code "189") (name "unconnected-(CMP40-N-PadOUT_M)") (class "Default")
      (node (ref "CMP40") (pin "OUT_M") (pinfunction "N_OUT_M") (pintype "output"))
    )
    (net (code "190") (name "unconnected-(CMP41-N-PadOUT_M)") (class "Default")
      (node (ref "CMP41") (pin "OUT_M") (pinfunction "N_OUT_M") (pintype "output"))
    )
    (net (code "191") (name "unconnected-(CMP44-N-PadOUT_M)") (class "Default")
      (node (ref "CMP44") (pin "OUT_M") (pinfunction "N_OUT_M") (pintype "output"))
    )
    (net (code "192") (name "unconnected-(CMP45-N-PadOUT_M)") (class "Default")
      (node (ref "CMP45") (pin "OUT_M") (pinfunction "N_OUT_M") (pintype "output"))
    )
    (net (code "193") (name "unconnected-(CMP47-OUT_13-PadP$14)") (class "Default")
      (node (ref "CMP47") (pin "P$14") (pinfunction "OUT_13_P$14") (pintype "output"))
    )
    (net (code "194") (name "unconnected-(CMP47-PadINPUT)") (class "Default")
      (node (ref "CMP47") (pin "INPUT") (pinfunction "INPUT_INPUT") (pintype "input"))
    )
    (net (code "195") (name "unconnected-(CMP57-OUT_14-PadP$15)") (class "Default")
      (node (ref "CMP57") (pin "P$15") (pinfunction "OUT_14_P$15") (pintype "output"))
    )
    (net (code "196") (name "unconnected-(CMP57-OUT_15-PadP$16)") (class "Default")
      (node (ref "CMP57") (pin "P$16") (pinfunction "OUT_15_P$16") (pintype "output"))
    )
    (net (code "197") (name "unconnected-(CMP57-PadINPUT)") (class "Default")
      (node (ref "CMP57") (pin "INPUT") (pinfunction "INPUT_INPUT") (pintype "input"))
    )
    (net (code "198") (name "unconnected-(CMP65-N-PadOUT_M)") (class "Default")
      (node (ref "CMP65") (pin "OUT_M") (pinfunction "N_OUT_M") (pintype "output"))
    )
    (net (code "199") (name "unconnected-(CMP66-N-PadOUT_M)") (class "Default")
      (node (ref "CMP66") (pin "OUT_M") (pinfunction "N_OUT_M") (pintype "output"))
    )
    (net (code "200") (name "unconnected-(CMP73-N-PadOUT_M)") (class "Default")
      (node (ref "CMP73") (pin "OUT_M") (pinfunction "N_OUT_M") (pintype "output"))
    )
    (net (code "201") (name "unconnected-(CMP86-N-PadOUT_M)") (class "Default")
      (node (ref "CMP86") (pin "OUT_M") (pinfunction "N_OUT_M") (pintype "output"))
    )
    (net (code "202") (name "unconnected-(CMP88-N-PadOUT_M)") (class "Default")
      (node (ref "CMP88") (pin "OUT_M") (pinfunction "N_OUT_M") (pintype "output"))
    )
    (net (code "203") (name "unconnected-(CMP90-OUT_2-PadP$3)") (class "Default")
      (node (ref "CMP90") (pin "P$3") (pinfunction "OUT_2_P$3") (pintype "output"))
    )
    (net (code "204") (name "unconnected-(CMP90-OUT_3-PadP$4)") (class "Default")
      (node (ref "CMP90") (pin "P$4") (pinfunction "OUT_3_P$4") (pintype "output"))
    )
    (net (code "205") (name "unconnected-(CMP90-OUT_4-PadP$5)") (class "Default")
      (node (ref "CMP90") (pin "P$5") (pinfunction "OUT_4_P$5") (pintype "output"))
    )
    (net (code "206") (name "unconnected-(CMP90-OUT_5-PadP$6)") (class "Default")
      (node (ref "CMP90") (pin "P$6") (pinfunction "OUT_5_P$6") (pintype "output"))
    )
    (net (code "207") (name "unconnected-(CMP90-OUT_6-PadP$7)") (class "Default")
      (node (ref "CMP90") (pin "P$7") (pinfunction "OUT_6_P$7") (pintype "output"))
    )
    (net (code "208") (name "unconnected-(CMP90-OUT_7-PadP$8)") (class "Default")
      (node (ref "CMP90") (pin "P$8") (pinfunction "OUT_7_P$8") (pintype "output"))
    )
    (net (code "209") (name "unconnected-(CMP90-OUT_8-PadP$9)") (class "Default")
      (node (ref "CMP90") (pin "P$9") (pinfunction "OUT_8_P$9") (pintype "output"))
    )
    (net (code "210") (name "unconnected-(CMP90-OUT_9-PadP$10)") (class "Default")
      (node (ref "CMP90") (pin "P$10") (pinfunction "OUT_9_P$10") (pintype "output"))
    )
    (net (code "211") (name "unconnected-(CMP90-OUT_10-PadP$11)") (class "Default")
      (node (ref "CMP90") (pin "P$11") (pinfunction "OUT_10_P$11") (pintype "output"))
    )
    (net (code "212") (name "unconnected-(CMP90-OUT_11-PadP$12)") (class "Default")
      (node (ref "CMP90") (pin "P$12") (pinfunction "OUT_11_P$12") (pintype "output"))
    )
    (net (code "213") (name "unconnected-(CMP90-OUT_12-PadP$13)") (class "Default")
      (node (ref "CMP90") (pin "P$13") (pinfunction "OUT_12_P$13") (pintype "output"))
    )
    (net (code "214") (name "unconnected-(CMP90-OUT_13-PadP$14)") (class "Default")
      (node (ref "CMP90") (pin "P$14") (pinfunction "OUT_13_P$14") (pintype "output"))
    )
    (net (code "215") (name "unconnected-(CMP90-OUT_14-PadP$15)") (class "Default")
      (node (ref "CMP90") (pin "P$15") (pinfunction "OUT_14_P$15") (pintype "output"))
    )
    (net (code "216") (name "unconnected-(CMP90-OUT_15-PadP$16)") (class "Default")
      (node (ref "CMP90") (pin "P$16") (pinfunction "OUT_15_P$16") (pintype "output"))
    )
    (net (code "217") (name "unconnected-(CMP90-PadINPUT)") (class "Default")
      (node (ref "CMP90") (pin "INPUT") (pinfunction "INPUT_INPUT") (pintype "input"))
    )
    (net (code "218") (name "unconnected-(CMP92-N-PadOUT_M)") (class "Default")
      (node (ref "CMP92") (pin "OUT_M") (pinfunction "N_OUT_M") (pintype "output"))
    )
    (net (code "219") (name "unconnected-(CMP98-N-PadOUT_M)") (class "Default")
      (node (ref "CMP98") (pin "OUT_M") (pinfunction "N_OUT_M") (pintype "output"))
    )
    (net (code "220") (name "unconnected-(CMP104-N-PadOUT_M)") (class "Default")
      (node (ref "CMP104") (pin "OUT_M") (pinfunction "N_OUT_M") (pintype "output"))
    )
  )
)
